# M8300B.net
KiCad netlist of a schematic drawn in EAGLE
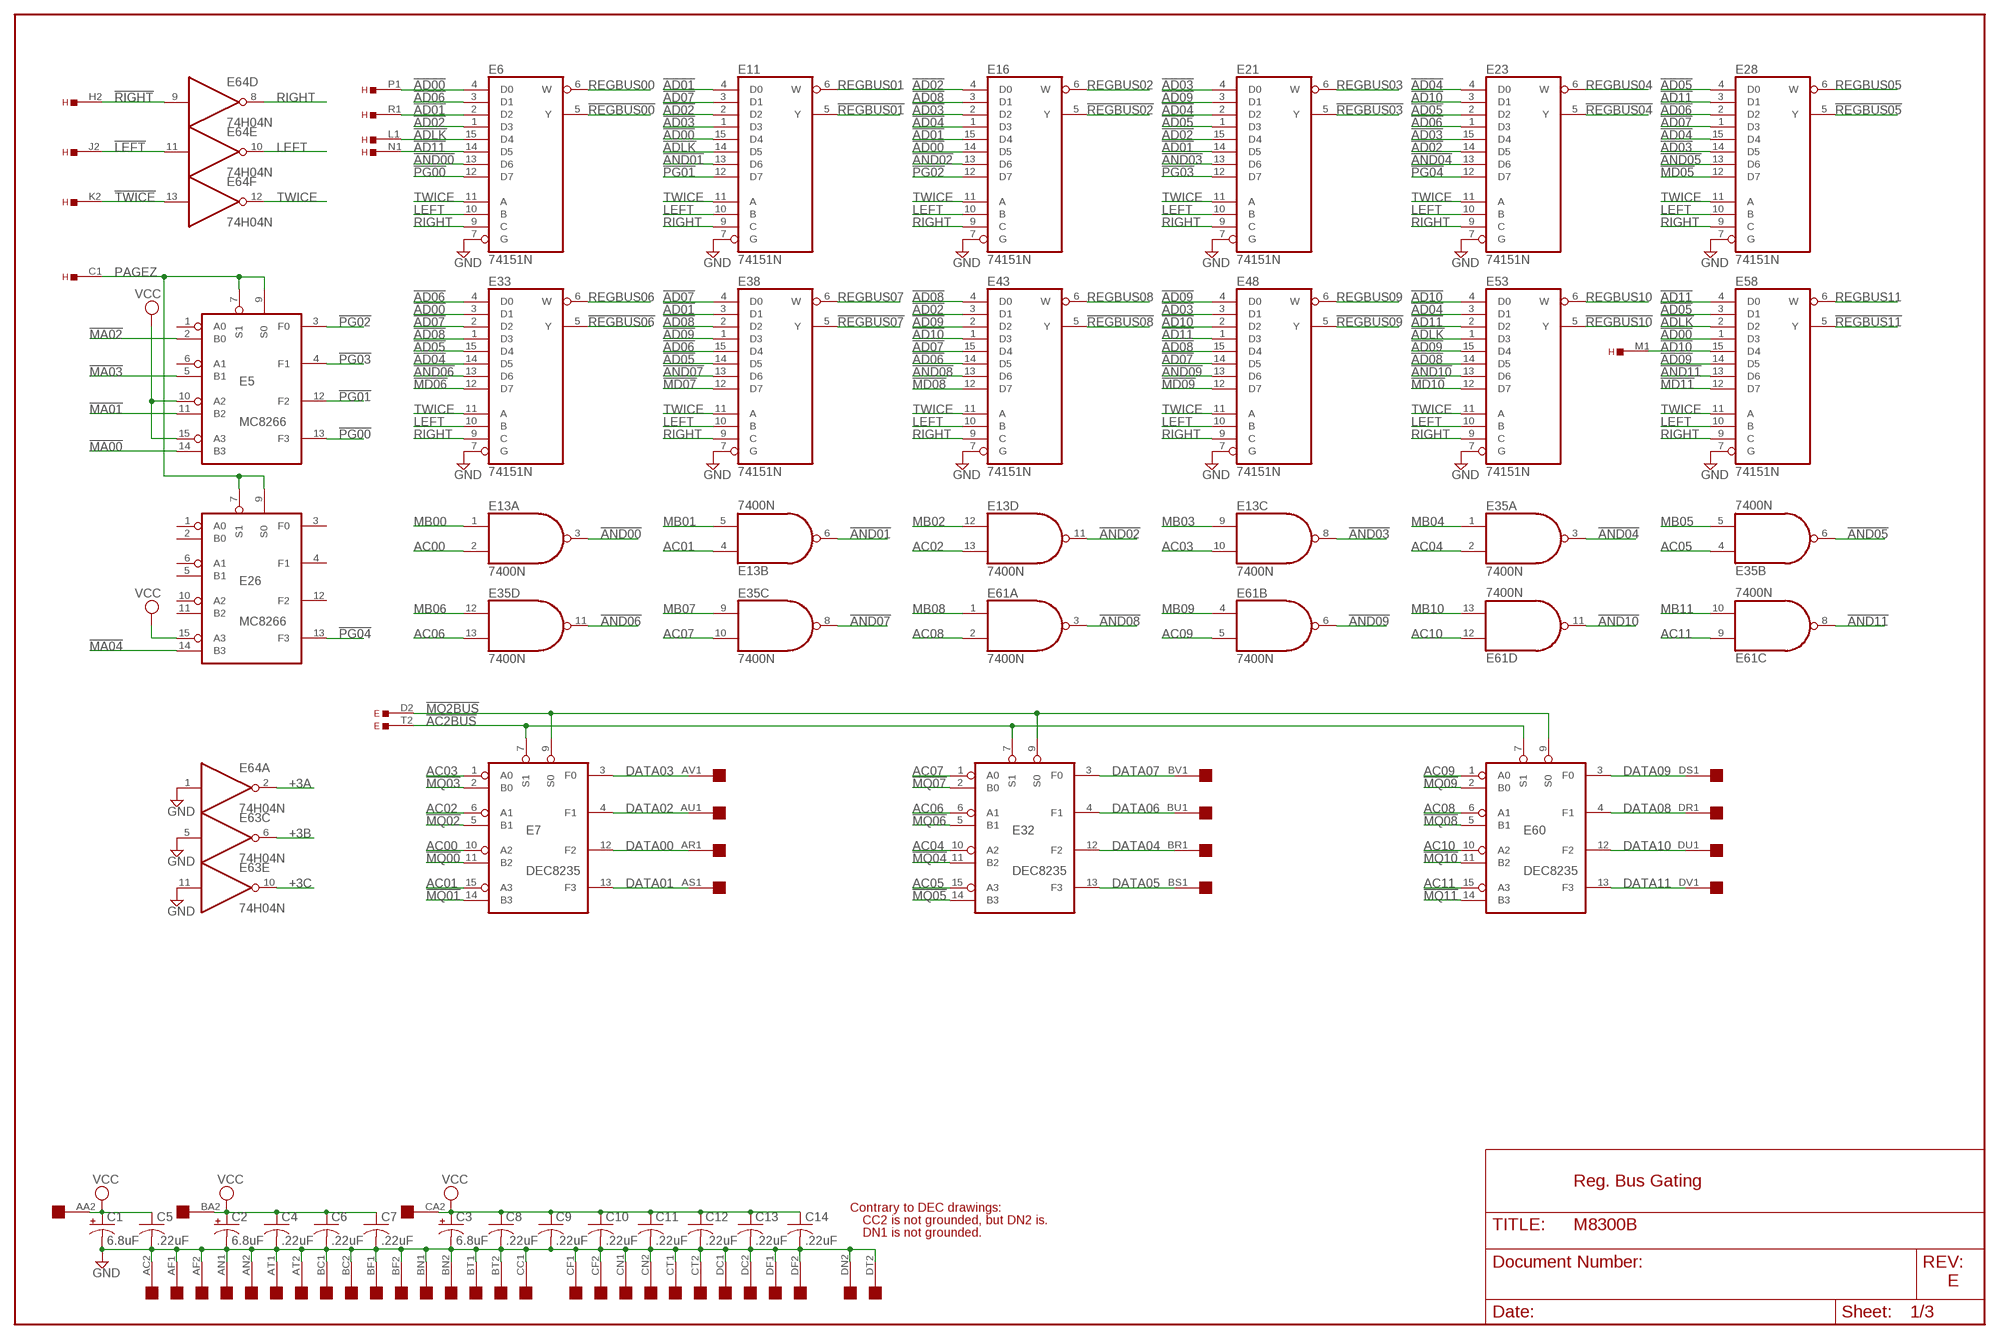
[diagram p0: schematic, sheet 1]
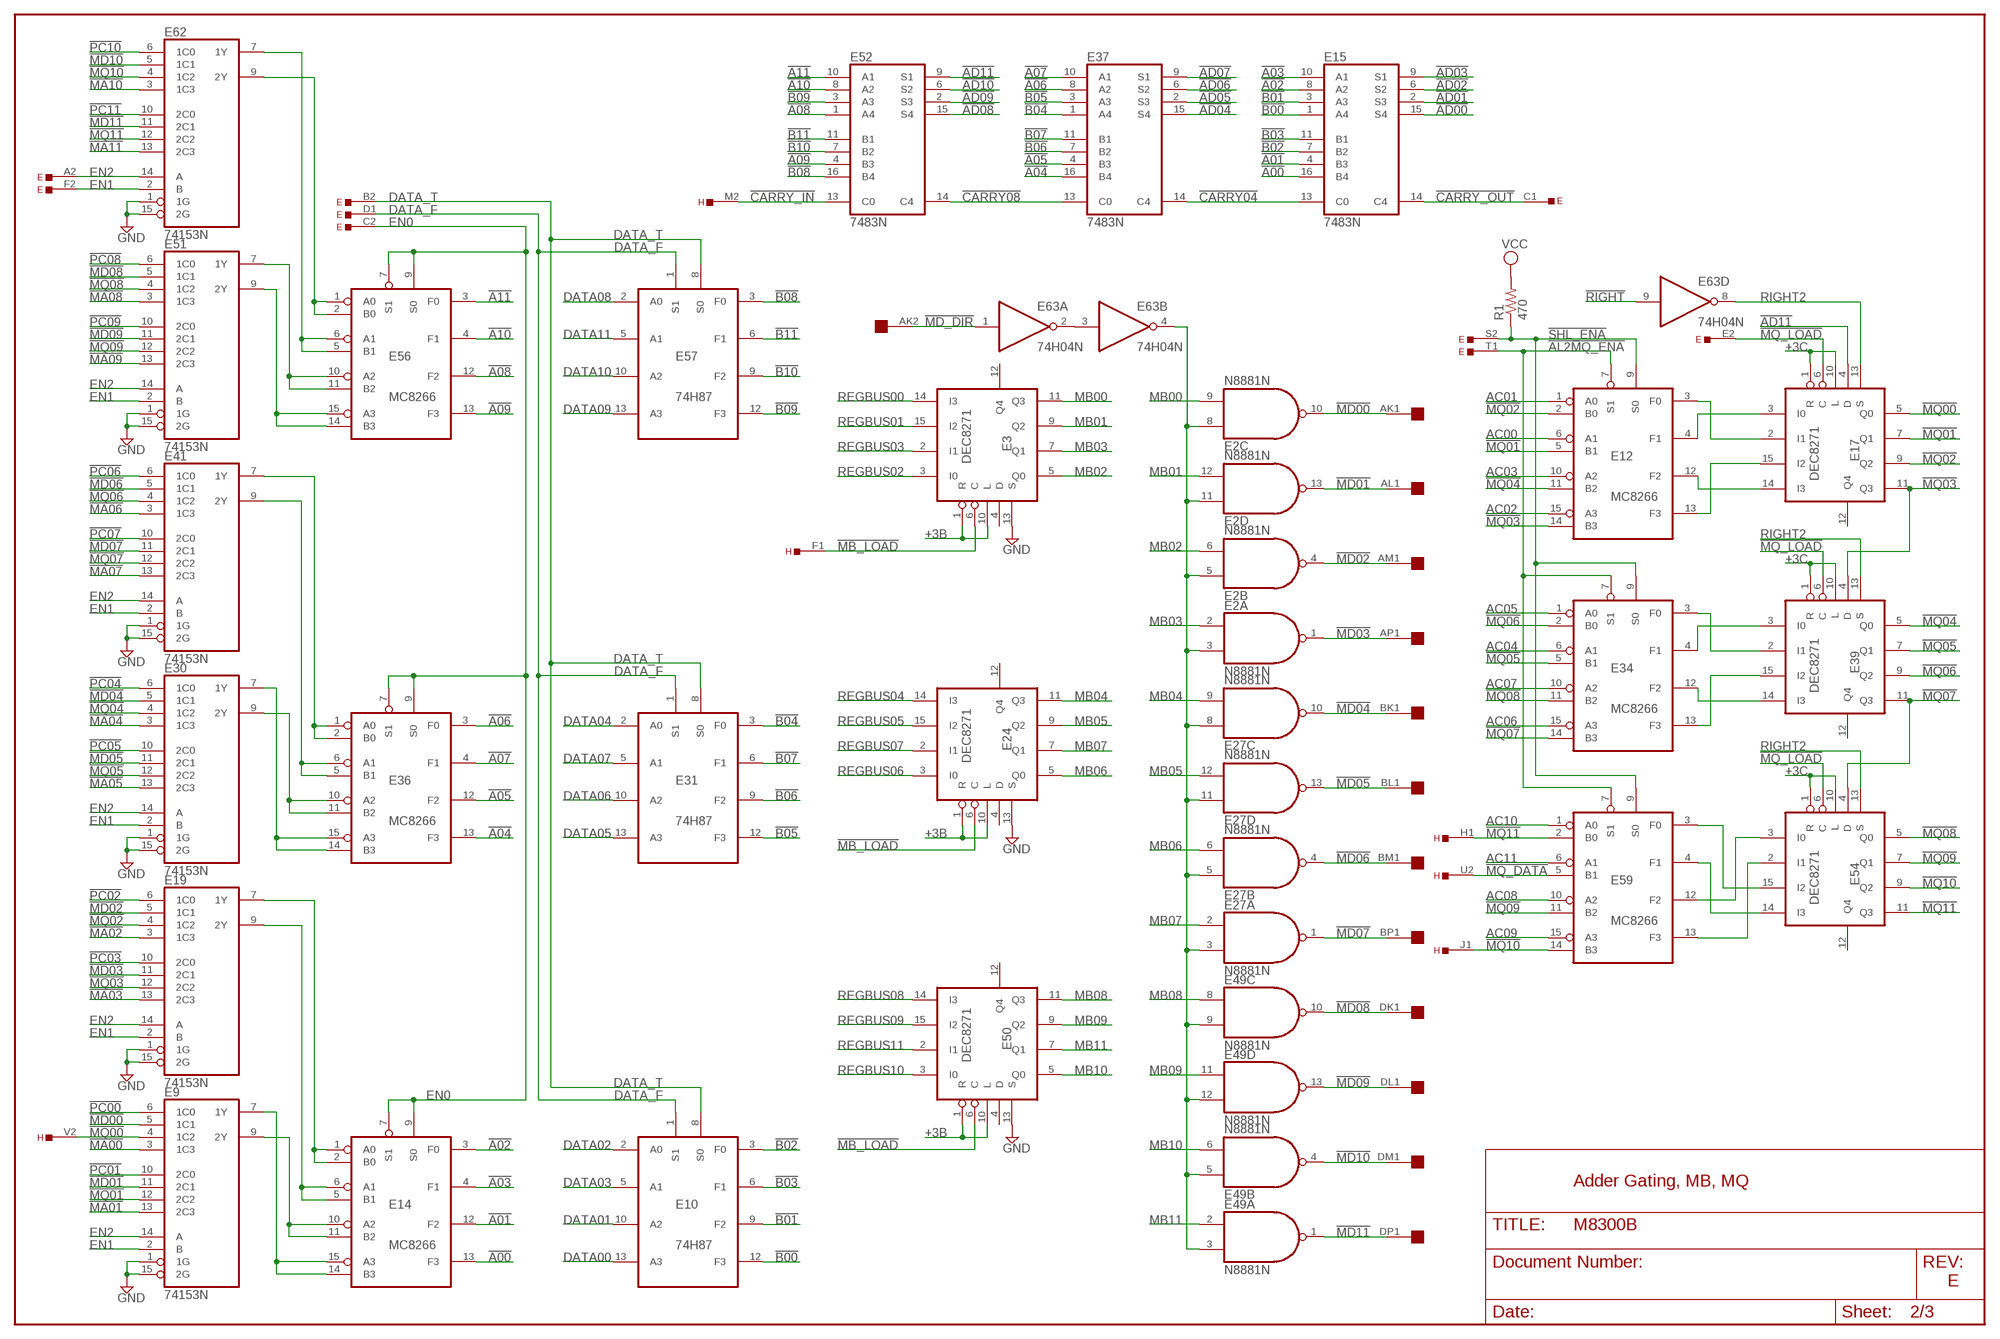
[diagram p1: schematic, sheet 2]
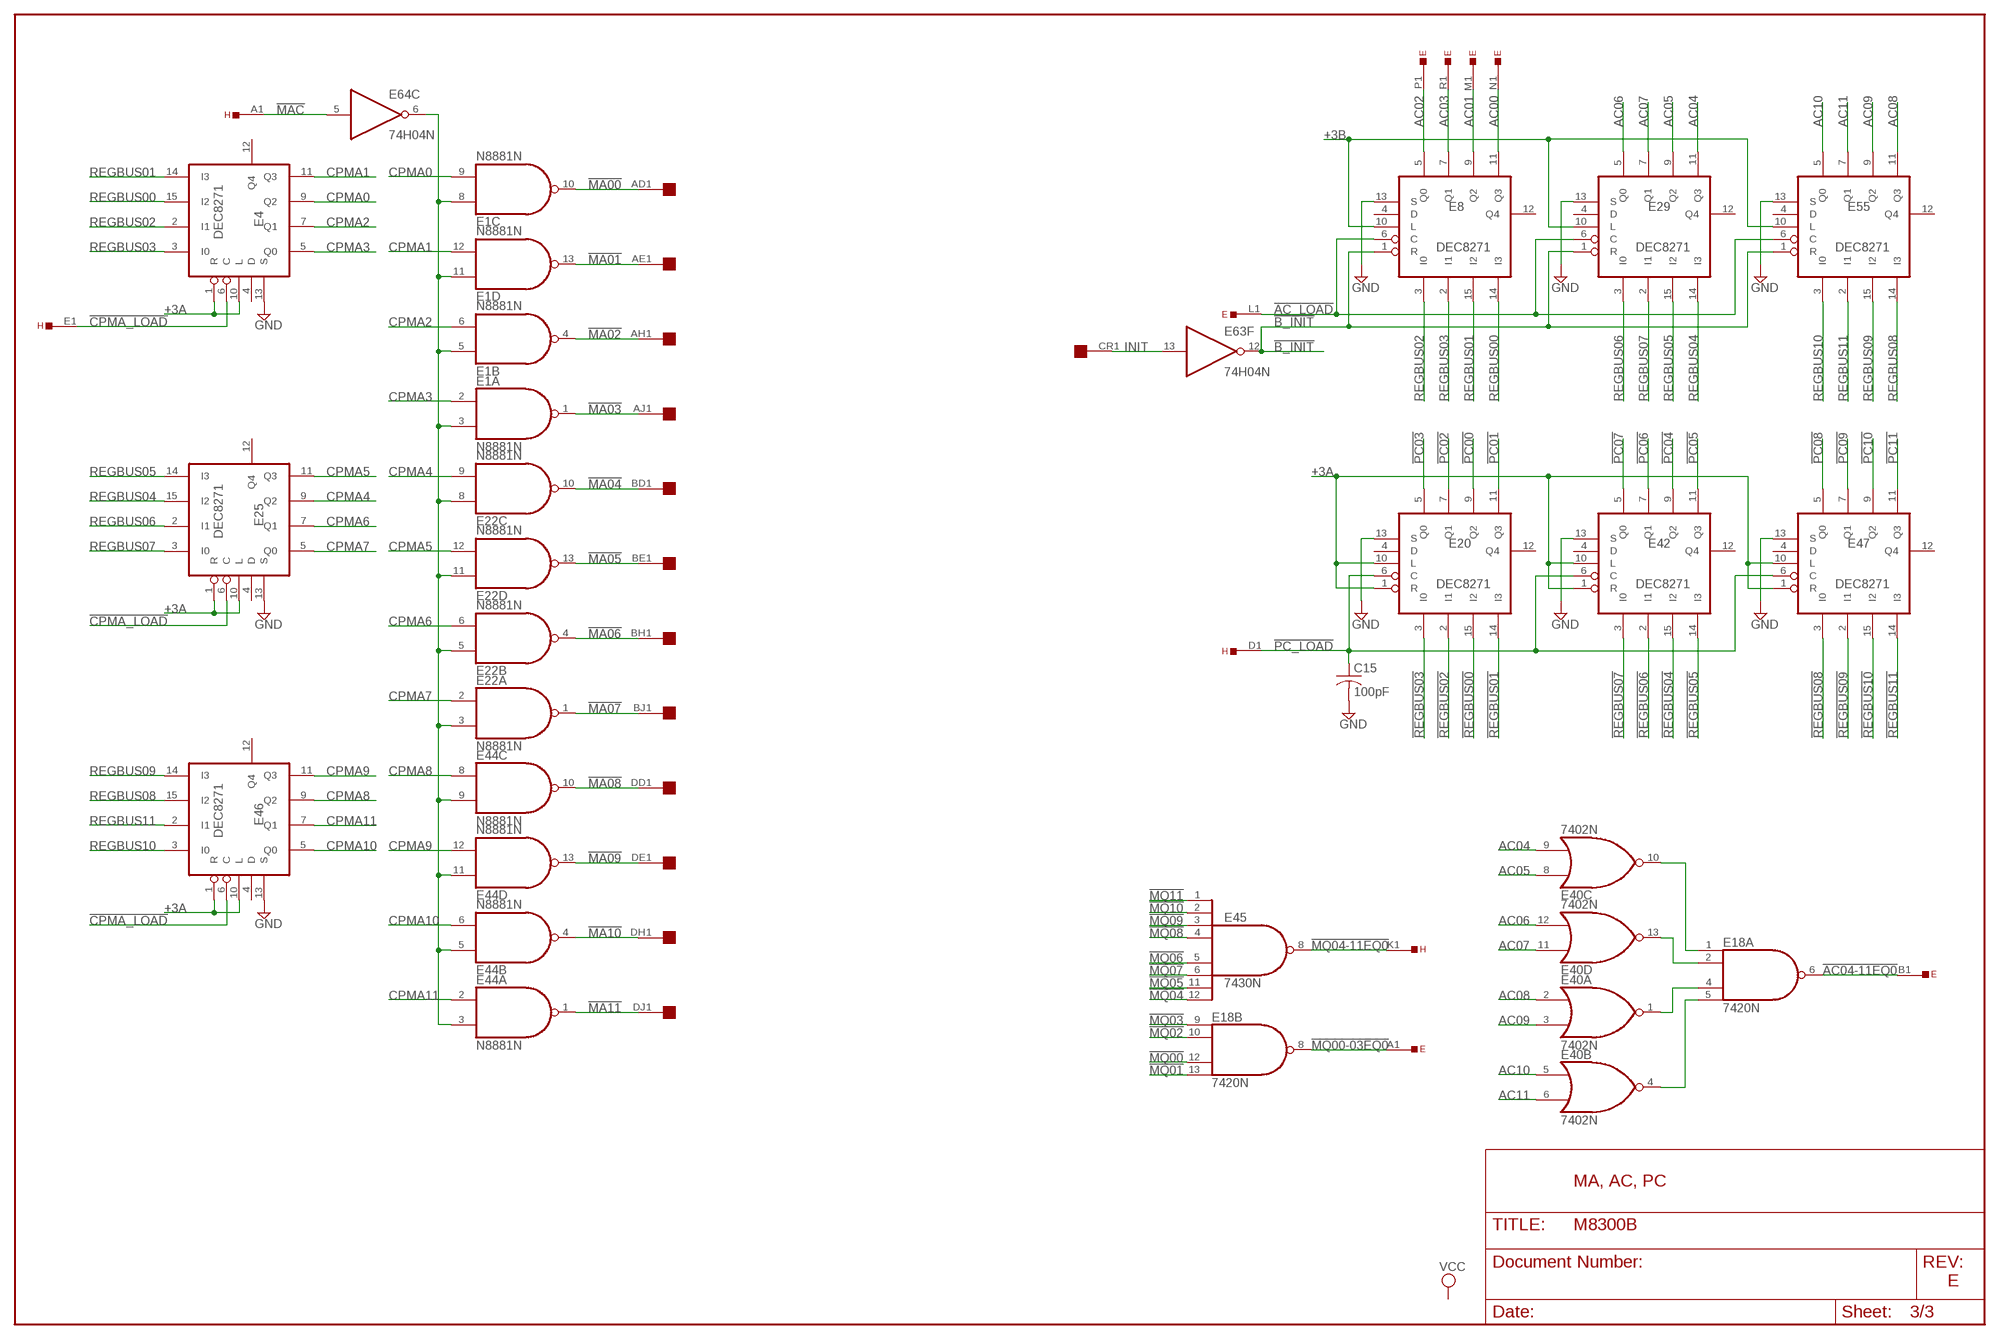
[diagram p2: schematic, sheet 3]

(export (version "E")
  (design (tool "Eeschema 10.0.6"))
  (components
    (comp (ref "E")
      (value "EDGE-TOP")
      (footprint "eagle-import:EDGE-CON2")
      (libsource (lib "eagle-import") (part "EDGE-TOP"))
    )
    (comp (ref "E2")
      (value "N8881N")
      (footprint "eagle-import:DIL14")
      (libsource (lib "eagle-import") (part "N8881N"))
    )
    (comp (ref "E3")
      (value "DEC8271")
      (footprint "eagle-import:DIL16")
      (libsource (lib "eagle-import") (part "DEC8271"))
    )
    (comp (ref "E9")
      (value "74153N")
      (footprint "eagle-import:DIL16")
      (libsource (lib "eagle-import") (part "74153NS"))
    )
    (comp (ref "E10")
      (value "74H87")
      (footprint "eagle-import:DIL14")
      (libsource (lib "eagle-import") (part "7487H"))
    )
    (comp (ref "E12")
      (value "MC8266")
      (footprint "eagle-import:DIL16")
      (libsource (lib "eagle-import") (part "MC8266"))
    )
    (comp (ref "E14")
      (value "MC8266")
      (footprint "eagle-import:DIL16")
      (libsource (lib "eagle-import") (part "MC8266"))
    )
    (comp (ref "E15")
      (value "7483N")
      (footprint "eagle-import:DIL16")
      (libsource (lib "eagle-import") (part "7483N"))
    )
    (comp (ref "E17")
      (value "DEC8271")
      (footprint "eagle-import:DIL16")
      (libsource (lib "eagle-import") (part "DEC8271"))
    )
    (comp (ref "E19")
      (value "74153N")
      (footprint "eagle-import:DIL16")
      (libsource (lib "eagle-import") (part "74153NS"))
    )
    (comp (ref "E24")
      (value "DEC8271")
      (footprint "eagle-import:DIL16")
      (libsource (lib "eagle-import") (part "DEC8271"))
    )
    (comp (ref "E27")
      (value "N8881N")
      (footprint "eagle-import:DIL14")
      (libsource (lib "eagle-import") (part "N8881N"))
    )
    (comp (ref "E30")
      (value "74153N")
      (footprint "eagle-import:DIL16")
      (libsource (lib "eagle-import") (part "74153NS"))
    )
    (comp (ref "E31")
      (value "74H87")
      (footprint "eagle-import:DIL14")
      (libsource (lib "eagle-import") (part "7487H"))
    )
    (comp (ref "E34")
      (value "MC8266")
      (footprint "eagle-import:DIL16")
      (libsource (lib "eagle-import") (part "MC8266"))
    )
    (comp (ref "E36")
      (value "MC8266")
      (footprint "eagle-import:DIL16")
      (libsource (lib "eagle-import") (part "MC8266"))
    )
    (comp (ref "E37")
      (value "7483N")
      (footprint "eagle-import:DIL16")
      (libsource (lib "eagle-import") (part "7483N"))
    )
    (comp (ref "E39")
      (value "DEC8271")
      (footprint "eagle-import:DIL16")
      (libsource (lib "eagle-import") (part "DEC8271"))
    )
    (comp (ref "E41")
      (value "74153N")
      (footprint "eagle-import:DIL16")
      (libsource (lib "eagle-import") (part "74153NS"))
    )
    (comp (ref "E49")
      (value "N8881N")
      (footprint "eagle-import:DIL14")
      (libsource (lib "eagle-import") (part "N8881N"))
    )
    (comp (ref "E50")
      (value "DEC8271")
      (footprint "eagle-import:DIL16")
      (libsource (lib "eagle-import") (part "DEC8271"))
    )
    (comp (ref "E51")
      (value "74153N")
      (footprint "eagle-import:DIL16")
      (libsource (lib "eagle-import") (part "74153NS"))
    )
    (comp (ref "E52")
      (value "7483N")
      (footprint "eagle-import:DIL16")
      (libsource (lib "eagle-import") (part "7483N"))
    )
    (comp (ref "E54")
      (value "DEC8271")
      (footprint "eagle-import:DIL16")
      (libsource (lib "eagle-import") (part "DEC8271"))
    )
    (comp (ref "E56")
      (value "MC8266")
      (footprint "eagle-import:DIL16")
      (libsource (lib "eagle-import") (part "MC8266"))
    )
    (comp (ref "E57")
      (value "74H87")
      (footprint "eagle-import:DIL14")
      (libsource (lib "eagle-import") (part "7487H"))
    )
    (comp (ref "E59")
      (value "MC8266")
      (footprint "eagle-import:DIL16")
      (libsource (lib "eagle-import") (part "MC8266"))
    )
    (comp (ref "E62")
      (value "74153N")
      (footprint "eagle-import:DIL16")
      (libsource (lib "eagle-import") (part "74153NS"))
    )
    (comp (ref "E63")
      (value "74H04N")
      (footprint "eagle-import:DIL14")
      (libsource (lib "eagle-import") (part "7404NS"))
    )
    (comp (ref "H")
      (value "EDGE-TOP")
      (footprint "eagle-import:EDGE-CON2")
      (libsource (lib "eagle-import") (part "EDGE-TOP"))
    )
    (comp (ref "R1")
      (value "470")
      (footprint "eagle-import:0207_10")
      (libsource (lib "eagle-import") (part "R-US_0207/10"))
    )
    (comp (ref "U$2")
      (value "QUAD")
      (footprint "eagle-import:EDGE-CON8")
      (libsource (lib "eagle-import") (part "QUAD"))
    )
    (comp (ref "C15")
      (value "100pF")
      (footprint "eagle-import:C063-025X075")
      (libsource (lib "eagle-import") (part "C-US"))
    )
    (comp (ref "E1")
      (value "N8881N")
      (footprint "eagle-import:DIL14")
      (libsource (lib "eagle-import") (part "N8881N"))
    )
    (comp (ref "E4")
      (value "DEC8271")
      (footprint "eagle-import:DIL16")
      (libsource (lib "eagle-import") (part "DEC8271"))
    )
    (comp (ref "E8")
      (value "DEC8271")
      (footprint "eagle-import:DIL16")
      (libsource (lib "eagle-import") (part "DEC8271"))
    )
    (comp (ref "E18")
      (value "7420N")
      (footprint "eagle-import:DIL14")
      (libsource (lib "eagle-import") (part "7420NS"))
    )
    (comp (ref "E20")
      (value "DEC8271")
      (footprint "eagle-import:DIL16")
      (libsource (lib "eagle-import") (part "DEC8271"))
    )
    (comp (ref "E22")
      (value "N8881N")
      (footprint "eagle-import:DIL14")
      (libsource (lib "eagle-import") (part "N8881N"))
    )
    (comp (ref "E25")
      (value "DEC8271")
      (footprint "eagle-import:DIL16")
      (libsource (lib "eagle-import") (part "DEC8271"))
    )
    (comp (ref "E29")
      (value "DEC8271")
      (footprint "eagle-import:DIL16")
      (libsource (lib "eagle-import") (part "DEC8271"))
    )
    (comp (ref "E40")
      (value "7402N")
      (footprint "eagle-import:DIL14")
      (libsource (lib "eagle-import") (part "7402N"))
    )
    (comp (ref "E42")
      (value "DEC8271")
      (footprint "eagle-import:DIL16")
      (libsource (lib "eagle-import") (part "DEC8271"))
    )
    (comp (ref "E44")
      (value "N8881N")
      (footprint "eagle-import:DIL14")
      (libsource (lib "eagle-import") (part "N8881N"))
    )
    (comp (ref "E45")
      (value "7430N")
      (footprint "eagle-import:DIL14")
      (libsource (lib "eagle-import") (part "7430N"))
    )
    (comp (ref "E46")
      (value "DEC8271")
      (footprint "eagle-import:DIL16")
      (libsource (lib "eagle-import") (part "DEC8271"))
    )
    (comp (ref "E47")
      (value "DEC8271")
      (footprint "eagle-import:DIL16")
      (libsource (lib "eagle-import") (part "DEC8271"))
    )
    (comp (ref "E55")
      (value "DEC8271")
      (footprint "eagle-import:DIL16")
      (libsource (lib "eagle-import") (part "DEC8271"))
    )
    (comp (ref "E64")
      (value "74H04N")
      (footprint "eagle-import:DIL14")
      (libsource (lib "eagle-import") (part "7404NS"))
    )
    (comp (ref "C1")
      (value "6.8uF")
      (footprint "eagle-import:E12-8")
      (libsource (lib "eagle-import") (part "CPOL-USE20-8AXIAL"))
    )
    (comp (ref "C2")
      (value "6.8uF")
      (footprint "eagle-import:E12-8")
      (libsource (lib "eagle-import") (part "CPOL-USE20-8AXIAL"))
    )
    (comp (ref "C3")
      (value "6.8uF")
      (footprint "eagle-import:E12-8")
      (libsource (lib "eagle-import") (part "CPOL-USE20-8AXIAL"))
    )
    (comp (ref "C4")
      (value ".22uF")
      (footprint "eagle-import:C063-025X075")
      (libsource (lib "eagle-import") (part "C-US"))
    )
    (comp (ref "C5")
      (value ".22uF")
      (footprint "eagle-import:C063-025X075")
      (libsource (lib "eagle-import") (part "C-US"))
    )
    (comp (ref "C6")
      (value ".22uF")
      (footprint "eagle-import:C063-025X075")
      (libsource (lib "eagle-import") (part "C-US"))
    )
    (comp (ref "C7")
      (value ".22uF")
      (footprint "eagle-import:C063-025X075")
      (libsource (lib "eagle-import") (part "C-US"))
    )
    (comp (ref "C8")
      (value ".22uF")
      (footprint "eagle-import:C063-025X075")
      (libsource (lib "eagle-import") (part "C-US"))
    )
    (comp (ref "C9")
      (value ".22uF")
      (footprint "eagle-import:C063-025X075")
      (libsource (lib "eagle-import") (part "C-US"))
    )
    (comp (ref "C10")
      (value ".22uF")
      (footprint "eagle-import:C063-025X075")
      (libsource (lib "eagle-import") (part "C-US"))
    )
    (comp (ref "C11")
      (value ".22uF")
      (footprint "eagle-import:C063-025X075")
      (libsource (lib "eagle-import") (part "C-US"))
    )
    (comp (ref "C12")
      (value ".22uF")
      (footprint "eagle-import:C063-025X075")
      (libsource (lib "eagle-import") (part "C-US"))
    )
    (comp (ref "C13")
      (value ".22uF")
      (footprint "eagle-import:C063-025X075")
      (libsource (lib "eagle-import") (part "C-US"))
    )
    (comp (ref "C14")
      (value ".22uF")
      (footprint "eagle-import:C063-025X075")
      (libsource (lib "eagle-import") (part "C-US"))
    )
    (comp (ref "E5")
      (value "MC8266")
      (footprint "eagle-import:DIL16")
      (libsource (lib "eagle-import") (part "MC8266"))
    )
    (comp (ref "E6")
      (value "74151N")
      (footprint "eagle-import:DIL16")
      (libsource (lib "eagle-import") (part "74151N"))
    )
    (comp (ref "E7")
      (value "DEC8235")
      (footprint "eagle-import:DIL16")
      (libsource (lib "eagle-import") (part "DEC8235"))
    )
    (comp (ref "E11")
      (value "74151N")
      (footprint "eagle-import:DIL16")
      (libsource (lib "eagle-import") (part "74151N"))
    )
    (comp (ref "E13")
      (value "7400N")
      (footprint "eagle-import:DIL14")
      (libsource (lib "eagle-import") (part "7400N"))
    )
    (comp (ref "E16")
      (value "74151N")
      (footprint "eagle-import:DIL16")
      (libsource (lib "eagle-import") (part "74151N"))
    )
    (comp (ref "E21")
      (value "74151N")
      (footprint "eagle-import:DIL16")
      (libsource (lib "eagle-import") (part "74151N"))
    )
    (comp (ref "E23")
      (value "74151N")
      (footprint "eagle-import:DIL16")
      (libsource (lib "eagle-import") (part "74151N"))
    )
    (comp (ref "E26")
      (value "MC8266")
      (footprint "eagle-import:DIL16")
      (libsource (lib "eagle-import") (part "MC8266"))
    )
    (comp (ref "E28")
      (value "74151N")
      (footprint "eagle-import:DIL16")
      (libsource (lib "eagle-import") (part "74151N"))
    )
    (comp (ref "E32")
      (value "DEC8235")
      (footprint "eagle-import:DIL16")
      (libsource (lib "eagle-import") (part "DEC8235"))
    )
    (comp (ref "E33")
      (value "74151N")
      (footprint "eagle-import:DIL16")
      (libsource (lib "eagle-import") (part "74151N"))
    )
    (comp (ref "E35")
      (value "7400N")
      (footprint "eagle-import:DIL14")
      (libsource (lib "eagle-import") (part "7400N"))
    )
    (comp (ref "E38")
      (value "74151N")
      (footprint "eagle-import:DIL16")
      (libsource (lib "eagle-import") (part "74151N"))
    )
    (comp (ref "E43")
      (value "74151N")
      (footprint "eagle-import:DIL16")
      (libsource (lib "eagle-import") (part "74151N"))
    )
    (comp (ref "E48")
      (value "74151N")
      (footprint "eagle-import:DIL16")
      (libsource (lib "eagle-import") (part "74151N"))
    )
    (comp (ref "E53")
      (value "74151N")
      (footprint "eagle-import:DIL16")
      (libsource (lib "eagle-import") (part "74151N"))
    )
    (comp (ref "E58")
      (value "74151N")
      (footprint "eagle-import:DIL16")
      (libsource (lib "eagle-import") (part "74151N"))
    )
    (comp (ref "E60")
      (value "DEC8235")
      (footprint "eagle-import:DIL16")
      (libsource (lib "eagle-import") (part "DEC8235"))
    )
    (comp (ref "E61")
      (value "7400N")
      (footprint "eagle-import:DIL14")
      (libsource (lib "eagle-import") (part "7400N"))
    )
  )
  (nets
    (net (code "1") (name "+3A") (class "Default")
      (node (ref "E20") (pin "1") (pinfunction "R_1") (pintype "input"))
      (node (ref "E20") (pin "10") (pinfunction "L_10") (pintype "input"))
      (node (ref "E25") (pin "1") (pinfunction "R_1") (pintype "input"))
      (node (ref "E25") (pin "10") (pinfunction "L_10") (pintype "input"))
      (node (ref "E4") (pin "1") (pinfunction "R_1") (pintype "input"))
      (node (ref "E4") (pin "10") (pinfunction "L_10") (pintype "input"))
      (node (ref "E42") (pin "1") (pinfunction "R_1") (pintype "input"))
      (node (ref "E42") (pin "10") (pinfunction "L_10") (pintype "input"))
      (node (ref "E46") (pin "1") (pinfunction "R_1") (pintype "input"))
      (node (ref "E46") (pin "10") (pinfunction "L_10") (pintype "input"))
      (node (ref "E47") (pin "1") (pinfunction "R_1") (pintype "input"))
      (node (ref "E47") (pin "10") (pinfunction "L_10") (pintype "input"))
      (node (ref "E64") (pin "2") (pinfunction "O_2") (pintype "output"))
    )
    (net (code "2") (name "+3B") (class "Default")
      (node (ref "E24") (pin "1") (pinfunction "R_1") (pintype "input"))
      (node (ref "E24") (pin "10") (pinfunction "L_10") (pintype "input"))
      (node (ref "E29") (pin "10") (pinfunction "L_10") (pintype "input"))
      (node (ref "E3") (pin "1") (pinfunction "R_1") (pintype "input"))
      (node (ref "E3") (pin "10") (pinfunction "L_10") (pintype "input"))
      (node (ref "E50") (pin "1") (pinfunction "R_1") (pintype "input"))
      (node (ref "E50") (pin "10") (pinfunction "L_10") (pintype "input"))
      (node (ref "E55") (pin "10") (pinfunction "L_10") (pintype "input"))
      (node (ref "E63") (pin "6") (pinfunction "O_6") (pintype "output"))
      (node (ref "E8") (pin "10") (pinfunction "L_10") (pintype "input"))
    )
    (net (code "3") (name "+3C") (class "Default")
      (node (ref "E17") (pin "1") (pinfunction "R_1") (pintype "input"))
      (node (ref "E17") (pin "10") (pinfunction "L_10") (pintype "input"))
      (node (ref "E39") (pin "1") (pinfunction "R_1") (pintype "input"))
      (node (ref "E39") (pin "10") (pinfunction "L_10") (pintype "input"))
      (node (ref "E54") (pin "1") (pinfunction "R_1") (pintype "input"))
      (node (ref "E54") (pin "10") (pinfunction "L_10") (pintype "input"))
      (node (ref "E63") (pin "10") (pinfunction "O_10") (pintype "output"))
    )
    (net (code "4") (name "AC00") (class "Default")
      (node (ref "E") (pin "N1") (pinfunction "P_N1") (pintype "passive"))
      (node (ref "E12") (pin "6") (pinfunction "A1_6") (pintype "input"))
      (node (ref "E13") (pin "2") (pinfunction "I1_2") (pintype "input"))
      (node (ref "E7") (pin "10") (pinfunction "A2_10") (pintype "input"))
      (node (ref "E8") (pin "11") (pinfunction "Q3_11") (pintype "output"))
    )
    (net (code "5") (name "AC01") (class "Default")
      (node (ref "E") (pin "M1") (pinfunction "P_M1") (pintype "passive"))
      (node (ref "E12") (pin "1") (pinfunction "A0_1") (pintype "input"))
      (node (ref "E13") (pin "4") (pinfunction "I0_4") (pintype "input"))
      (node (ref "E7") (pin "15") (pinfunction "A3_15") (pintype "input"))
      (node (ref "E8") (pin "9") (pinfunction "Q2_9") (pintype "output"))
    )
    (net (code "6") (name "AC02") (class "Default")
      (node (ref "E") (pin "P1") (pinfunction "P_P1") (pintype "passive"))
      (node (ref "E12") (pin "15") (pinfunction "A3_15") (pintype "input"))
      (node (ref "E13") (pin "13") (pinfunction "I1_13") (pintype "input"))
      (node (ref "E7") (pin "6") (pinfunction "A1_6") (pintype "input"))
      (node (ref "E8") (pin "5") (pinfunction "Q0_5") (pintype "output"))
    )
    (net (code "7") (name "AC03") (class "Default")
      (node (ref "E") (pin "R1") (pinfunction "P_R1") (pintype "passive"))
      (node (ref "E12") (pin "10") (pinfunction "A2_10") (pintype "input"))
      (node (ref "E13") (pin "10") (pinfunction "I1_10") (pintype "input"))
      (node (ref "E7") (pin "1") (pinfunction "A0_1") (pintype "input"))
      (node (ref "E8") (pin "7") (pinfunction "Q1_7") (pintype "output"))
    )
    (net (code "8") (name "AC04") (class "Default")
      (node (ref "E29") (pin "11") (pinfunction "Q3_11") (pintype "output"))
      (node (ref "E32") (pin "10") (pinfunction "A2_10") (pintype "input"))
      (node (ref "E34") (pin "6") (pinfunction "A1_6") (pintype "input"))
      (node (ref "E35") (pin "2") (pinfunction "I1_2") (pintype "input"))
      (node (ref "E40") (pin "9") (pinfunction "I1_9") (pintype "input"))
    )
    (net (code "9") (name "AC05") (class "Default")
      (node (ref "E29") (pin "9") (pinfunction "Q2_9") (pintype "output"))
      (node (ref "E32") (pin "15") (pinfunction "A3_15") (pintype "input"))
      (node (ref "E34") (pin "1") (pinfunction "A0_1") (pintype "input"))
      (node (ref "E35") (pin "4") (pinfunction "I0_4") (pintype "input"))
      (node (ref "E40") (pin "8") (pinfunction "I0_8") (pintype "input"))
    )
    (net (code "10") (name "AC06") (class "Default")
      (node (ref "E29") (pin "5") (pinfunction "Q0_5") (pintype "output"))
      (node (ref "E32") (pin "6") (pinfunction "A1_6") (pintype "input"))
      (node (ref "E34") (pin "15") (pinfunction "A3_15") (pintype "input"))
      (node (ref "E35") (pin "13") (pinfunction "I1_13") (pintype "input"))
      (node (ref "E40") (pin "12") (pinfunction "I1_12") (pintype "input"))
    )
    (net (code "11") (name "AC07") (class "Default")
      (node (ref "E29") (pin "7") (pinfunction "Q1_7") (pintype "output"))
      (node (ref "E32") (pin "1") (pinfunction "A0_1") (pintype "input"))
      (node (ref "E34") (pin "10") (pinfunction "A2_10") (pintype "input"))
      (node (ref "E35") (pin "10") (pinfunction "I1_10") (pintype "input"))
      (node (ref "E40") (pin "11") (pinfunction "I0_11") (pintype "input"))
    )
    (net (code "12") (name "AC08") (class "Default")
      (node (ref "E40") (pin "2") (pinfunction "I0_2") (pintype "input"))
      (node (ref "E55") (pin "11") (pinfunction "Q3_11") (pintype "output"))
      (node (ref "E59") (pin "10") (pinfunction "A2_10") (pintype "input"))
      (node (ref "E60") (pin "6") (pinfunction "A1_6") (pintype "input"))
      (node (ref "E61") (pin "2") (pinfunction "I1_2") (pintype "input"))
    )
    (net (code "13") (name "AC09") (class "Default")
      (node (ref "E40") (pin "3") (pinfunction "I1_3") (pintype "input"))
      (node (ref "E55") (pin "9") (pinfunction "Q2_9") (pintype "output"))
      (node (ref "E59") (pin "15") (pinfunction "A3_15") (pintype "input"))
      (node (ref "E60") (pin "1") (pinfunction "A0_1") (pintype "input"))
      (node (ref "E61") (pin "5") (pinfunction "I1_5") (pintype "input"))
    )
    (net (code "14") (name "AC10") (class "Default")
      (node (ref "E40") (pin "5") (pinfunction "I0_5") (pintype "input"))
      (node (ref "E55") (pin "5") (pinfunction "Q0_5") (pintype "output"))
      (node (ref "E59") (pin "1") (pinfunction "A0_1") (pintype "input"))
      (node (ref "E60") (pin "10") (pinfunction "A2_10") (pintype "input"))
      (node (ref "E61") (pin "12") (pinfunction "I0_12") (pintype "input"))
    )
    (net (code "15") (name "AC11") (class "Default")
      (node (ref "E40") (pin "6") (pinfunction "I1_6") (pintype "input"))
      (node (ref "E55") (pin "7") (pinfunction "Q1_7") (pintype "output"))
      (node (ref "E59") (pin "6") (pinfunction "A1_6") (pintype "input"))
      (node (ref "E60") (pin "15") (pinfunction "A3_15") (pintype "input"))
      (node (ref "E61") (pin "9") (pinfunction "I0_9") (pintype "input"))
    )
    (net (code "16") (name "CPMA0") (class "Default")
      (node (ref "E1") (pin "9") (pinfunction "I1_9") (pintype "input"))
      (node (ref "E4") (pin "9") (pinfunction "Q2_9") (pintype "output"))
    )
    (net (code "17") (name "CPMA1") (class "Default")
      (node (ref "E1") (pin "12") (pinfunction "I1_12") (pintype "input"))
      (node (ref "E4") (pin "11") (pinfunction "Q3_11") (pintype "output"))
    )
    (net (code "18") (name "CPMA2") (class "Default")
      (node (ref "E1") (pin "6") (pinfunction "I1_6") (pintype "input"))
      (node (ref "E4") (pin "7") (pinfunction "Q1_7") (pintype "output"))
    )
    (net (code "19") (name "CPMA3") (class "Default")
      (node (ref "E1") (pin "2") (pinfunction "I0_2") (pintype "input"))
      (node (ref "E4") (pin "5") (pinfunction "Q0_5") (pintype "output"))
    )
    (net (code "20") (name "CPMA4") (class "Default")
      (node (ref "E22") (pin "9") (pinfunction "I1_9") (pintype "input"))
      (node (ref "E25") (pin "9") (pinfunction "Q2_9") (pintype "output"))
    )
    (net (code "21") (name "CPMA5") (class "Default")
      (node (ref "E22") (pin "12") (pinfunction "I1_12") (pintype "input"))
      (node (ref "E25") (pin "11") (pinfunction "Q3_11") (pintype "output"))
    )
    (net (code "22") (name "CPMA6") (class "Default")
      (node (ref "E22") (pin "6") (pinfunction "I1_6") (pintype "input"))
      (node (ref "E25") (pin "7") (pinfunction "Q1_7") (pintype "output"))
    )
    (net (code "23") (name "CPMA7") (class "Default")
      (node (ref "E22") (pin "2") (pinfunction "I0_2") (pintype "input"))
      (node (ref "E25") (pin "5") (pinfunction "Q0_5") (pintype "output"))
    )
    (net (code "24") (name "CPMA8") (class "Default")
      (node (ref "E44") (pin "8") (pinfunction "I0_8") (pintype "input"))
      (node (ref "E46") (pin "9") (pinfunction "Q2_9") (pintype "output"))
    )
    (net (code "25") (name "CPMA9") (class "Default")
      (node (ref "E44") (pin "12") (pinfunction "I1_12") (pintype "input"))
      (node (ref "E46") (pin "11") (pinfunction "Q3_11") (pintype "output"))
    )
    (net (code "26") (name "CPMA10") (class "Default")
      (node (ref "E44") (pin "6") (pinfunction "I1_6") (pintype "input"))
      (node (ref "E46") (pin "5") (pinfunction "Q0_5") (pintype "output"))
    )
    (net (code "27") (name "CPMA11") (class "Default")
      (node (ref "E44") (pin "2") (pinfunction "I0_2") (pintype "input"))
      (node (ref "E46") (pin "7") (pinfunction "Q1_7") (pintype "output"))
    )
    (net (code "28") (name "DATA00") (class "Default")
      (node (ref "E10") (pin "13") (pinfunction "A3_13") (pintype "input"))
      (node (ref "E7") (pin "12") (pinfunction "F2_12") (pintype "open_collector"))
      (node (ref "U$2") (pin "AR1") (pinfunction "1_AR1") (pintype "bidirectional"))
    )
    (net (code "29") (name "DATA01") (class "Default")
      (node (ref "E10") (pin "10") (pinfunction "A2_10") (pintype "input"))
      (node (ref "E7") (pin "13") (pinfunction "F3_13") (pintype "open_collector"))
      (node (ref "U$2") (pin "AS1") (pinfunction "1_AS1") (pintype "bidirectional"))
    )
    (net (code "30") (name "DATA02") (class "Default")
      (node (ref "E10") (pin "2") (pinfunction "A0_2") (pintype "input"))
      (node (ref "E7") (pin "4") (pinfunction "F1_4") (pintype "open_collector"))
      (node (ref "U$2") (pin "AU1") (pinfunction "1_AU1") (pintype "bidirectional"))
    )
    (net (code "31") (name "DATA03") (class "Default")
      (node (ref "E10") (pin "5") (pinfunction "A1_5") (pintype "input"))
      (node (ref "E7") (pin "3") (pinfunction "F0_3") (pintype "open_collector"))
      (node (ref "U$2") (pin "AV1") (pinfunction "1_AV1") (pintype "bidirectional"))
    )
    (net (code "32") (name "DATA04") (class "Default")
      (node (ref "E31") (pin "2") (pinfunction "A0_2") (pintype "input"))
      (node (ref "E32") (pin "12") (pinfunction "F2_12") (pintype "open_collector"))
      (node (ref "U$2") (pin "BR1") (pinfunction "1_BR1") (pintype "bidirectional"))
    )
    (net (code "33") (name "DATA05") (class "Default")
      (node (ref "E31") (pin "13") (pinfunction "A3_13") (pintype "input"))
      (node (ref "E32") (pin "13") (pinfunction "F3_13") (pintype "open_collector"))
      (node (ref "U$2") (pin "BS1") (pinfunction "1_BS1") (pintype "bidirectional"))
    )
    (net (code "34") (name "DATA06") (class "Default")
      (node (ref "E31") (pin "10") (pinfunction "A2_10") (pintype "input"))
      (node (ref "E32") (pin "4") (pinfunction "F1_4") (pintype "open_collector"))
      (node (ref "U$2") (pin "BU1") (pinfunction "1_BU1") (pintype "bidirectional"))
    )
    (net (code "35") (name "DATA07") (class "Default")
      (node (ref "E31") (pin "5") (pinfunction "A1_5") (pintype "input"))
      (node (ref "E32") (pin "3") (pinfunction "F0_3") (pintype "open_collector"))
      (node (ref "U$2") (pin "BV1") (pinfunction "1_BV1") (pintype "bidirectional"))
    )
    (net (code "36") (name "DATA08") (class "Default")
      (node (ref "E57") (pin "2") (pinfunction "A0_2") (pintype "input"))
      (node (ref "E60") (pin "4") (pinfunction "F1_4") (pintype "open_collector"))
      (node (ref "U$2") (pin "DR1") (pinfunction "1_DR1") (pintype "bidirectional"))
    )
    (net (code "37") (name "DATA09") (class "Default")
      (node (ref "E57") (pin "13") (pinfunction "A3_13") (pintype "input"))
      (node (ref "E60") (pin "3") (pinfunction "F0_3") (pintype "open_collector"))
      (node (ref "U$2") (pin "DS1") (pinfunction "1_DS1") (pintype "bidirectional"))
    )
    (net (code "38") (name "DATA10") (class "Default")
      (node (ref "E57") (pin "10") (pinfunction "A2_10") (pintype "input"))
      (node (ref "E60") (pin "12") (pinfunction "F2_12") (pintype "open_collector"))
      (node (ref "U$2") (pin "DU1") (pinfunction "1_DU1") (pintype "bidirectional"))
    )
    (net (code "39") (name "DATA11") (class "Default")
      (node (ref "E57") (pin "5") (pinfunction "A1_5") (pintype "input"))
      (node (ref "E60") (pin "13") (pinfunction "F3_13") (pintype "open_collector"))
      (node (ref "U$2") (pin "DV1") (pinfunction "1_DV1") (pintype "bidirectional"))
    )
    (net (code "40") (name "DATA_F") (class "Default")
      (node (ref "E") (pin "D1") (pinfunction "P_D1") (pintype "passive"))
      (node (ref "E10") (pin "1") (pinfunction "S1_1") (pintype "input"))
      (node (ref "E31") (pin "1") (pinfunction "S1_1") (pintype "input"))
      (node (ref "E57") (pin "1") (pinfunction "S1_1") (pintype "input"))
    )
    (net (code "41") (name "DATA_T") (class "Default")
      (node (ref "E") (pin "B2") (pinfunction "P_B2") (pintype "passive"))
      (node (ref "E10") (pin "8") (pinfunction "S0_8") (pintype "input"))
      (node (ref "E31") (pin "8") (pinfunction "S0_8") (pintype "input"))
      (node (ref "E57") (pin "8") (pinfunction "S0_8") (pintype "input"))
    )
    (net (code "42") (name "EN0") (class "Default")
      (node (ref "E") (pin "C2") (pinfunction "P_C2") (pintype "passive"))
      (node (ref "E14") (pin "7") (pinfunction "S1_7") (pintype "input"))
      (node (ref "E14") (pin "9") (pinfunction "S0_9") (pintype "input"))
      (node (ref "E36") (pin "7") (pinfunction "S1_7") (pintype "input"))
      (node (ref "E36") (pin "9") (pinfunction "S0_9") (pintype "input"))
      (node (ref "E56") (pin "7") (pinfunction "S1_7") (pintype "input"))
      (node (ref "E56") (pin "9") (pinfunction "S0_9") (pintype "input"))
    )
    (net (code "43") (name "EN1") (class "Default")
      (node (ref "E") (pin "F2") (pinfunction "P_F2") (pintype "passive"))
      (node (ref "E19") (pin "2") (pinfunction "B_2") (pintype "input"))
      (node (ref "E30") (pin "2") (pinfunction "B_2") (pintype "input"))
      (node (ref "E41") (pin "2") (pinfunction "B_2") (pintype "input"))
      (node (ref "E51") (pin "2") (pinfunction "B_2") (pintype "input"))
      (node (ref "E62") (pin "2") (pinfunction "B_2") (pintype "input"))
      (node (ref "E9") (pin "2") (pinfunction "B_2") (pintype "input"))
    )
    (net (code "44") (name "EN2") (class "Default")
      (node (ref "E") (pin "A2") (pinfunction "P_A2") (pintype "passive"))
      (node (ref "E19") (pin "14") (pinfunction "A_14") (pintype "input"))
      (node (ref "E30") (pin "14") (pinfunction "A_14") (pintype "input"))
      (node (ref "E41") (pin "14") (pinfunction "A_14") (pintype "input"))
      (node (ref "E51") (pin "14") (pinfunction "A_14") (pintype "input"))
      (node (ref "E62") (pin "14") (pinfunction "A_14") (pintype "input"))
      (node (ref "E9") (pin "14") (pinfunction "A_14") (pintype "input"))
    )
    (net (code "45") (name "GND") (class "Default")
      (node (ref "C1") (pin "-") (pinfunction "-_-") (pintype "passive"))
      (node (ref "C10") (pin "2") (pinfunction "2_2") (pintype "passive"))
      (node (ref "C11") (pin "2") (pinfunction "2_2") (pintype "passive"))
      (node (ref "C12") (pin "2") (pinfunction "2_2") (pintype "passive"))
      (node (ref "C13") (pin "2") (pinfunction "2_2") (pintype "passive"))
      (node (ref "C14") (pin "2") (pinfunction "2_2") (pintype "passive"))
      (node (ref "C15") (pin "2") (pinfunction "2_2") (pintype "passive"))
      (node (ref "C2") (pin "-") (pinfunction "-_-") (pintype "passive"))
      (node (ref "C3") (pin "-") (pinfunction "-_-") (pintype "passive"))
      (node (ref "C4") (pin "2") (pinfunction "2_2") (pintype "passive"))
      (node (ref "C5") (pin "2") (pinfunction "2_2") (pintype "passive"))
      (node (ref "C6") (pin "2") (pinfunction "2_2") (pintype "passive"))
      (node (ref "C7") (pin "2") (pinfunction "2_2") (pintype "passive"))
      (node (ref "C8") (pin "2") (pinfunction "2_2") (pintype "passive"))
      (node (ref "C9") (pin "2") (pinfunction "2_2") (pintype "passive"))
      (node (ref "E11") (pin "7") (pinfunction "G_7") (pintype "input"))
      (node (ref "E16") (pin "7") (pinfunction "G_7") (pintype "input"))
      (node (ref "E19") (pin "1") (pinfunction "1G_1") (pintype "input"))
      (node (ref "E19") (pin "15") (pinfunction "2G_15") (pintype "input"))
      (node (ref "E20") (pin "13") (pinfunction "S_13") (pintype "input"))
      (node (ref "E21") (pin "7") (pinfunction "G_7") (pintype "input"))
      (node (ref "E23") (pin "7") (pinfunction "G_7") (pintype "input"))
      (node (ref "E24") (pin "13") (pinfunction "S_13") (pintype "input"))
      (node (ref "E25") (pin "13") (pinfunction "S_13") (pintype "input"))
      (node (ref "E28") (pin "7") (pinfunction "G_7") (pintype "input"))
      (node (ref "E29") (pin "13") (pinfunction "S_13") (pintype "input"))
      (node (ref "E3") (pin "13") (pinfunction "S_13") (pintype "input"))
      (node (ref "E30") (pin "1") (pinfunction "1G_1") (pintype "input"))
      (node (ref "E30") (pin "15") (pinfunction "2G_15") (pintype "input"))
      (node (ref "E33") (pin "7") (pinfunction "G_7") (pintype "input"))
      (node (ref "E38") (pin "7") (pinfunction "G_7") (pintype "input"))
      (node (ref "E4") (pin "13") (pinfunction "S_13") (pintype "input"))
      (node (ref "E41") (pin "1") (pinfunction "1G_1") (pintype "input"))
      (node (ref "E41") (pin "15") (pinfunction "2G_15") (pintype "input"))
      (node (ref "E42") (pin "13") (pinfunction "S_13") (pintype "input"))
      (node (ref "E43") (pin "7") (pinfunction "G_7") (pintype "input"))
      (node (ref "E46") (pin "13") (pinfunction "S_13") (pintype "input"))
      (node (ref "E47") (pin "13") (pinfunction "S_13") (pintype "input"))
      (node (ref "E48") (pin "7") (pinfunction "G_7") (pintype "input"))
      (node (ref "E50") (pin "13") (pinfunction "S_13") (pintype "input"))
      (node (ref "E51") (pin "1") (pinfunction "1G_1") (pintype "input"))
      (node (ref "E51") (pin "15") (pinfunction "2G_15") (pintype "input"))
      (node (ref "E53") (pin "7") (pinfunction "G_7") (pintype "input"))
      (node (ref "E55") (pin "13") (pinfunction "S_13") (pintype "input"))
      (node (ref "E58") (pin "7") (pinfunction "G_7") (pintype "input"))
      (node (ref "E6") (pin "7") (pinfunction "G_7") (pintype "input"))
      (node (ref "E62") (pin "1") (pinfunction "1G_1") (pintype "input"))
      (node (ref "E62") (pin "15") (pinfunction "2G_15") (pintype "input"))
      (node (ref "E63") (pin "11") (pinfunction "I_11") (pintype "input"))
      (node (ref "E63") (pin "5") (pinfunction "I_5") (pintype "input"))
      (node (ref "E64") (pin "1") (pinfunction "I_1") (pintype "input"))
      (node (ref "E8") (pin "13") (pinfunction "S_13") (pintype "input"))
      (node (ref "E9") (pin "1") (pinfunction "1G_1") (pintype "input"))
      (node (ref "E9") (pin "15") (pinfunction "2G_15") (pintype "input"))
      (node (ref "U$2") (pin "AC2") (pinfunction "1_AC2") (pintype "bidirectional"))
      (node (ref "U$2") (pin "AF1") (pinfunction "1_AF1") (pintype "bidirectional"))
      (node (ref "U$2") (pin "AF2") (pinfunction "1_AF2") (pintype "bidirectional"))
      (node (ref "U$2") (pin "AN1") (pinfunction "1_AN1") (pintype "bidirectional"))
      (node (ref "U$2") (pin "AN2") (pinfunction "1_AN2") (pintype "bidirectional"))
      (node (ref "U$2") (pin "AT1") (pinfunction "1_AT1") (pintype "bidirectional"))
      (node (ref "U$2") (pin "AT2") (pinfunction "1_AT2") (pintype "bidirectional"))
      (node (ref "U$2") (pin "BC1") (pinfunction "1_BC1") (pintype "bidirectional"))
      (node (ref "U$2") (pin "BC2") (pinfunction "1_BC2") (pintype "bidirectional"))
      (node (ref "U$2") (pin "BF1") (pinfunction "1_BF1") (pintype "bidirectional"))
      (node (ref "U$2") (pin "BF2") (pinfunction "1_BF2") (pintype "bidirectional"))
      (node (ref "U$2") (pin "BN1") (pinfunction "1_BN1") (pintype "bidirectional"))
      (node (ref "U$2") (pin "BN2") (pinfunction "1_BN2") (pintype "bidirectional"))
      (node (ref "U$2") (pin "BT1") (pinfunction "1_BT1") (pintype "bidirectional"))
      (node (ref "U$2") (pin "BT2") (pinfunction "1_BT2") (pintype "bidirectional"))
      (node (ref "U$2") (pin "CC1") (pinfunction "1_CC1") (pintype "bidirectional"))
      (node (ref "U$2") (pin "CF1") (pinfunction "1_CF1") (pintype "bidirectional"))
      (node (ref "U$2") (pin "CF2") (pinfunction "1_CF2") (pintype "bidirectional"))
      (node (ref "U$2") (pin "CN1") (pinfunction "1_CN1") (pintype "bidirectional"))
      (node (ref "U$2") (pin "CN2") (pinfunction "1_CN2") (pintype "bidirectional"))
      (node (ref "U$2") (pin "CT1") (pinfunction "1_CT1") (pintype "bidirectional"))
      (node (ref "U$2") (pin "CT2") (pinfunction "1_CT2") (pintype "bidirectional"))
      (node (ref "U$2") (pin "DC1") (pinfunction "1_DC1") (pintype "bidirectional"))
      (node (ref "U$2") (pin "DC2") (pinfunction "1_DC2") (pintype "bidirectional"))
      (node (ref "U$2") (pin "DF1") (pinfunction "1_DF1") (pintype "bidirectional"))
      (node (ref "U$2") (pin "DF2") (pinfunction "1_DF2") (pintype "bidirectional"))
      (node (ref "U$2") (pin "DN2") (pinfunction "1_DN2") (pintype "bidirectional"))
      (node (ref "U$2") (pin "DT2") (pinfunction "1_DT2") (pintype "bidirectional"))
    )
    (net (code "46") (name "INIT") (class "Default")
      (node (ref "E63") (pin "13") (pinfunction "I_13") (pintype "input"))
      (node (ref "U$2") (pin "CR1") (pinfunction "1_CR1") (pintype "bidirectional"))
    )
    (net (code "47") (name "LEFT") (class "Default")
      (node (ref "E11") (pin "10") (pinfunction "B_10") (pintype "input"))
      (node (ref "E16") (pin "10") (pinfunction "B_10") (pintype "input"))
      (node (ref "E21") (pin "10") (pinfunction "B_10") (pintype "input"))
      (node (ref "E23") (pin "10") (pinfunction "B_10") (pintype "input"))
      (node (ref "E28") (pin "10") (pinfunction "B_10") (pintype "input"))
      (node (ref "E33") (pin "10") (pinfunction "B_10") (pintype "input"))
      (node (ref "E38") (pin "10") (pinfunction "B_10") (pintype "input"))
      (node (ref "E43") (pin "10") (pinfunction "B_10") (pintype "input"))
      (node (ref "E48") (pin "10") (pinfunction "B_10") (pintype "input"))
      (node (ref "E53") (pin "10") (pinfunction "B_10") (pintype "input"))
      (node (ref "E58") (pin "10") (pinfunction "B_10") (pintype "input"))
      (node (ref "E6") (pin "10") (pinfunction "B_10") (pintype "input"))
      (node (ref "E64") (pin "10") (pinfunction "O_10") (pintype "output"))
    )
    (net (code "48") (name "MB00") (class "Default")
      (node (ref "E13") (pin "1") (pinfunction "I0_1") (pintype "input"))
      (node (ref "E2") (pin "9") (pinfunction "I1_9") (pintype "input"))
      (node (ref "E3") (pin "11") (pinfunction "Q3_11") (pintype "output"))
    )
    (net (code "49") (name "MB01") (class "Default")
      (node (ref "E13") (pin "5") (pinfunction "I1_5") (pintype "input"))
      (node (ref "E2") (pin "12") (pinfunction "I1_12") (pintype "input"))
      (node (ref "E3") (pin "9") (pinfunction "Q2_9") (pintype "output"))
    )
    (net (code "50") (name "MB02") (class "Default")
      (node (ref "E13") (pin "12") (pinfunction "I0_12") (pintype "input"))
      (node (ref "E2") (pin "6") (pinfunction "I1_6") (pintype "input"))
      (node (ref "E3") (pin "5") (pinfunction "Q0_5") (pintype "output"))
    )
    (net (code "51") (name "MB03") (class "Default")
      (node (ref "E13") (pin "9") (pinfunction "I0_9") (pintype "input"))
      (node (ref "E2") (pin "2") (pinfunction "I0_2") (pintype "input"))
      (node (ref "E3") (pin "7") (pinfunction "Q1_7") (pintype "output"))
    )
    (net (code "52") (name "MB04") (class "Default")
      (node (ref "E24") (pin "11") (pinfunction "Q3_11") (pintype "output"))
      (node (ref "E27") (pin "9") (pinfunction "I1_9") (pintype "input"))
      (node (ref "E35") (pin "1") (pinfunction "I0_1") (pintype "input"))
    )
    (net (code "53") (name "MB05") (class "Default")
      (node (ref "E24") (pin "9") (pinfunction "Q2_9") (pintype "output"))
      (node (ref "E27") (pin "12") (pinfunction "I1_12") (pintype "input"))
      (node (ref "E35") (pin "5") (pinfunction "I1_5") (pintype "input"))
    )
    (net (code "54") (name "MB06") (class "Default")
      (node (ref "E24") (pin "5") (pinfunction "Q0_5") (pintype "output"))
      (node (ref "E27") (pin "6") (pinfunction "I1_6") (pintype "input"))
      (node (ref "E35") (pin "12") (pinfunction "I0_12") (pintype "input"))
    )
    (net (code "55") (name "MB07") (class "Default")
      (node (ref "E24") (pin "7") (pinfunction "Q1_7") (pintype "output"))
      (node (ref "E27") (pin "2") (pinfunction "I0_2") (pintype "input"))
      (node (ref "E35") (pin "9") (pinfunction "I0_9") (pintype "input"))
    )
    (net (code "56") (name "MB08") (class "Default")
      (node (ref "E49") (pin "8") (pinfunction "I0_8") (pintype "input"))
      (node (ref "E50") (pin "11") (pinfunction "Q3_11") (pintype "output"))
      (node (ref "E61") (pin "1") (pinfunction "I0_1") (pintype "input"))
    )
    (net (code "57") (name "MB09") (class "Default")
      (node (ref "E49") (pin "11") (pinfunction "I0_11") (pintype "input"))
      (node (ref "E50") (pin "9") (pinfunction "Q2_9") (pintype "output"))
      (node (ref "E61") (pin "4") (pinfunction "I0_4") (pintype "input"))
    )
    (net (code "58") (name "MB10") (class "Default")
      (node (ref "E49") (pin "6") (pinfunction "I1_6") (pintype "input"))
      (node (ref "E50") (pin "5") (pinfunction "Q0_5") (pintype "output"))
      (node (ref "E61") (pin "13") (pinfunction "I1_13") (pintype "input"))
    )
    (net (code "59") (name "MB11") (class "Default")
      (node (ref "E49") (pin "2") (pinfunction "I0_2") (pintype "input"))
      (node (ref "E50") (pin "7") (pinfunction "Q1_7") (pintype "output"))
      (node (ref "E61") (pin "10") (pinfunction "I1_10") (pintype "input"))
    )
    (net (code "60") (name "Net-(E1A-I1)") (class "Default")
      (node (ref "E1") (pin "11") (pinfunction "I0_11") (pintype "input"))
      (node (ref "E1") (pin "3") (pinfunction "I1_3") (pintype "input"))
      (node (ref "E1") (pin "5") (pinfunction "I0_5") (pintype "input"))
      (node (ref "E1") (pin "8") (pinfunction "I0_8") (pintype "input"))
      (node (ref "E22") (pin "11") (pinfunction "I0_11") (pintype "input"))
      (node (ref "E22") (pin "3") (pinfunction "I1_3") (pintype "input"))
      (node (ref "E22") (pin "5") (pinfunction "I0_5") (pintype "input"))
      (node (ref "E22") (pin "8") (pinfunction "I0_8") (pintype "input"))
      (node (ref "E44") (pin "11") (pinfunction "I0_11") (pintype "input"))
      (node (ref "E44") (pin "3") (pinfunction "I1_3") (pintype "input"))
      (node (ref "E44") (pin "5") (pinfunction "I0_5") (pintype "input"))
      (node (ref "E44") (pin "9") (pinfunction "I1_9") (pintype "input"))
      (node (ref "E64") (pin "6") (pinfunction "O_6") (pintype "output"))
    )
    (net (code "61") (name "Net-(E12A-F0)") (class "Default")
      (node (ref "E12") (pin "3") (pinfunction "F0_3") (pintype "output"))
      (node (ref "E17") (pin "2") (pinfunction "I1_2") (pintype "input"))
    )
    (net (code "62") (name "Net-(E12A-F1)") (class "Default")
      (node (ref "E12") (pin "4") (pinfunction "F1_4") (pintype "output"))
      (node (ref "E17") (pin "3") (pinfunction "I0_3") (pintype "input"))
    )
    (net (code "63") (name "Net-(E12A-F2)") (class "Default")
      (node (ref "E12") (pin "12") (pinfunction "F2_12") (pintype "output"))
      (node (ref "E17") (pin "14") (pinfunction "I3_14") (pintype "input"))
    )
    (net (code "64") (name "Net-(E12A-F3)") (class "Default")
      (node (ref "E12") (pin "13") (pinfunction "F3_13") (pintype "output"))
      (node (ref "E17") (pin "15") (pinfunction "I2_15") (pintype "input"))
    )
    (net (code "65") (name "Net-(E14A-A0)") (class "Default")
      (node (ref "E14") (pin "1") (pinfunction "A0_1") (pintype "input"))
      (node (ref "E14") (pin "2") (pinfunction "B0_2") (pintype "input"))
      (node (ref "E19") (pin "7") (pinfunction "1Y_7") (pintype "output"))
    )
    (net (code "66") (name "Net-(E14A-A1)") (class "Default")
      (node (ref "E14") (pin "5") (pinfunction "B1_5") (pintype "input"))
      (node (ref "E14") (pin "6") (pinfunction "A1_6") (pintype "input"))
      (node (ref "E19") (pin "9") (pinfunction "2Y_9") (pintype "output"))
    )
    (net (code "67") (name "Net-(E14A-A2)") (class "Default")
      (node (ref "E14") (pin "10") (pinfunction "A2_10") (pintype "input"))
      (node (ref "E14") (pin "11") (pinfunction "B2_11") (pintype "input"))
      (node (ref "E9") (pin "9") (pinfunction "2Y_9") (pintype "output"))
    )
    (net (code "68") (name "Net-(E14A-A3)") (class "Default")
      (node (ref "E14") (pin "14") (pinfunction "B3_14") (pintype "input"))
      (node (ref "E14") (pin "15") (pinfunction "A3_15") (pintype "input"))
      (node (ref "E9") (pin "7") (pinfunction "1Y_7") (pintype "output"))
    )
    (net (code "69") (name "Net-(E18A-I0)") (class "Default")
      (node (ref "E18") (pin "1") (pinfunction "I0_1") (pintype "input"))
      (node (ref "E40") (pin "10") (pinfunction "O_10") (pintype "output"))
    )
    (net (code "70") (name "Net-(E18A-I1)") (class "Default")
      (node (ref "E18") (pin "2") (pinfunction "I1_2") (pintype "input"))
      (node (ref "E40") (pin "13") (pinfunction "O_13") (pintype "output"))
    )
    (net (code "71") (name "Net-(E18A-I2)") (class "Default")
      (node (ref "E18") (pin "4") (pinfunction "I2_4") (pintype "input"))
      (node (ref "E40") (pin "1") (pinfunction "O_1") (pintype "output"))
    )
    (net (code "72") (name "Net-(E18A-I3)") (class "Default")
      (node (ref "E18") (pin "5") (pinfunction "I3_5") (pintype "input"))
      (node (ref "E40") (pin "4") (pinfunction "O_4") (pintype "output"))
    )
    (net (code "73") (name "Net-(E27A-I1)") (class "Default")
      (node (ref "E2") (pin "11") (pinfunction "I0_11") (pintype "input"))
      (node (ref "E2") (pin "3") (pinfunction "I1_3") (pintype "input"))
      (node (ref "E2") (pin "5") (pinfunction "I0_5") (pintype "input"))
      (node (ref "E2") (pin "8") (pinfunction "I0_8") (pintype "input"))
      (node (ref "E27") (pin "11") (pinfunction "I0_11") (pintype "input"))
      (node (ref "E27") (pin "3") (pinfunction "I1_3") (pintype "input"))
      (node (ref "E27") (pin "5") (pinfunction "I0_5") (pintype "input"))
      (node (ref "E27") (pin "8") (pinfunction "I0_8") (pintype "input"))
      (node (ref "E49") (pin "12") (pinfunction "I1_12") (pintype "input"))
      (node (ref "E49") (pin "3") (pinfunction "I1_3") (pintype "input"))
      (node (ref "E49") (pin "5") (pinfunction "I0_5") (pintype "input"))
      (node (ref "E49") (pin "9") (pinfunction "I1_9") (pintype "input"))
      (node (ref "E63") (pin "4") (pinfunction "O_4") (pintype "output"))
    )
    (net (code "74") (name "Net-(E30A-1Y)") (class "Default")
      (node (ref "E30") (pin "7") (pinfunction "1Y_7") (pintype "output"))
      (node (ref "E36") (pin "14") (pinfunction "B3_14") (pintype "input"))
      (node (ref "E36") (pin "15") (pinfunction "A3_15") (pintype "input"))
    )
    (net (code "75") (name "Net-(E30A-2Y)") (class "Default")
      (node (ref "E30") (pin "9") (pinfunction "2Y_9") (pintype "output"))
      (node (ref "E36") (pin "10") (pinfunction "A2_10") (pintype "input"))
      (node (ref "E36") (pin "11") (pinfunction "B2_11") (pintype "input"))
    )
    (net (code "76") (name "Net-(E34A-F0)") (class "Default")
      (node (ref "E34") (pin "3") (pinfunction "F0_3") (pintype "output"))
      (node (ref "E39") (pin "2") (pinfunction "I1_2") (pintype "input"))
    )
    (net (code "77") (name "Net-(E34A-F1)") (class "Default")
      (node (ref "E34") (pin "4") (pinfunction "F1_4") (pintype "output"))
      (node (ref "E39") (pin "3") (pinfunction "I0_3") (pintype "input"))
    )
    (net (code "78") (name "Net-(E34A-F2)") (class "Default")
      (node (ref "E34") (pin "12") (pinfunction "F2_12") (pintype "output"))
      (node (ref "E39") (pin "14") (pinfunction "I3_14") (pintype "input"))
    )
    (net (code "79") (name "Net-(E34A-F3)") (class "Default")
      (node (ref "E34") (pin "13") (pinfunction "F3_13") (pintype "output"))
      (node (ref "E39") (pin "15") (pinfunction "I2_15") (pintype "input"))
    )
    (net (code "80") (name "Net-(E36A-A0)") (class "Default")
      (node (ref "E36") (pin "1") (pinfunction "A0_1") (pintype "input"))
      (node (ref "E36") (pin "2") (pinfunction "B0_2") (pintype "input"))
      (node (ref "E41") (pin "7") (pinfunction "1Y_7") (pintype "output"))
    )
    (net (code "81") (name "Net-(E36A-A1)") (class "Default")
      (node (ref "E36") (pin "5") (pinfunction "B1_5") (pintype "input"))
      (node (ref "E36") (pin "6") (pinfunction "A1_6") (pintype "input"))
      (node (ref "E41") (pin "9") (pinfunction "2Y_9") (pintype "output"))
    )
    (net (code "82") (name "Net-(E51A-1Y)") (class "Default")
      (node (ref "E51") (pin "7") (pinfunction "1Y_7") (pintype "output"))
      (node (ref "E56") (pin "10") (pinfunction "A2_10") (pintype "input"))
      (node (ref "E56") (pin "11") (pinfunction "B2_11") (pintype "input"))
    )
    (net (code "83") (name "Net-(E51A-2Y)") (class "Default")
      (node (ref "E51") (pin "9") (pinfunction "2Y_9") (pintype "output"))
      (node (ref "E56") (pin "14") (pinfunction "B3_14") (pintype "input"))
      (node (ref "E56") (pin "15") (pinfunction "A3_15") (pintype "input"))
    )
    (net (code "84") (name "Net-(E54A-I0)") (class "Default")
      (node (ref "E54") (pin "3") (pinfunction "I0_3") (pintype "input"))
      (node (ref "E59") (pin "12") (pinfunction "F2_12") (pintype "output"))
    )
    (net (code "85") (name "Net-(E54A-I1)") (class "Default")
      (node (ref "E54") (pin "2") (pinfunction "I1_2") (pintype "input"))
      (node (ref "E59") (pin "13") (pinfunction "F3_13") (pintype "output"))
    )
    (net (code "86") (name "Net-(E54A-I2)") (class "Default")
      (node (ref "E54") (pin "15") (pinfunction "I2_15") (pintype "input"))
      (node (ref "E59") (pin "3") (pinfunction "F0_3") (pintype "output"))
    )
    (net (code "87") (name "Net-(E54A-I3)") (class "Default")
      (node (ref "E54") (pin "14") (pinfunction "I3_14") (pintype "input"))
      (node (ref "E59") (pin "4") (pinfunction "F1_4") (pintype "output"))
    )
    (net (code "88") (name "Net-(E56A-A0)") (class "Default")
      (node (ref "E56") (pin "1") (pinfunction "A0_1") (pintype "input"))
      (node (ref "E56") (pin "2") (pinfunction "B0_2") (pintype "input"))
      (node (ref "E62") (pin "9") (pinfunction "2Y_9") (pintype "output"))
    )
    (net (code "89") (name "Net-(E56A-A1)") (class "Default")
      (node (ref "E56") (pin "5") (pinfunction "B1_5") (pintype "input"))
      (node (ref "E56") (pin "6") (pinfunction "A1_6") (pintype "input"))
      (node (ref "E62") (pin "7") (pinfunction "1Y_7") (pintype "output"))
    )
    (net (code "90") (name "Net-(E63A-O)") (class "Default")
      (node (ref "E63") (pin "2") (pinfunction "O_2") (pintype "output"))
      (node (ref "E63") (pin "3") (pinfunction "I_3") (pintype "input"))
    )
    (net (code "91") (name "PAGEZ") (class "Default")
      (node (ref "E26") (pin "7") (pinfunction "S1_7") (pintype "input"))
      (node (ref "E26") (pin "9") (pinfunction "S0_9") (pintype "input"))
      (node (ref "E5") (pin "7") (pinfunction "S1_7") (pintype "input"))
      (node (ref "E5") (pin "9") (pinfunction "S0_9") (pintype "input"))
      (node (ref "H") (pin "C1") (pinfunction "P_C1") (pintype "passive"))
    )
    (net (code "92") (name "REGBUS00") (class "Default")
      (node (ref "E3") (pin "14") (pinfunction "I3_14") (pintype "input"))
      (node (ref "E4") (pin "15") (pinfunction "I2_15") (pintype "input"))
      (node (ref "E6") (pin "6") (pinfunction "W_6") (pintype "output"))
      (node (ref "E8") (pin "14") (pinfunction "I3_14") (pintype "input"))
    )
    (net (code "93") (name "REGBUS01") (class "Default")
      (node (ref "E11") (pin "6") (pinfunction "W_6") (pintype "output"))
      (node (ref "E3") (pin "15") (pinfunction "I2_15") (pintype "input"))
      (node (ref "E4") (pin "14") (pinfunction "I3_14") (pintype "input"))
      (node (ref "E8") (pin "15") (pinfunction "I2_15") (pintype "input"))
    )
    (net (code "94") (name "REGBUS02") (class "Default")
      (node (ref "E16") (pin "6") (pinfunction "W_6") (pintype "output"))
      (node (ref "E3") (pin "3") (pinfunction "I0_3") (pintype "input"))
      (node (ref "E4") (pin "2") (pinfunction "I1_2") (pintype "input"))
      (node (ref "E8") (pin "3") (pinfunction "I0_3") (pintype "input"))
    )
    (net (code "95") (name "REGBUS03") (class "Default")
      (node (ref "E21") (pin "6") (pinfunction "W_6") (pintype "output"))
      (node (ref "E3") (pin "2") (pinfunction "I1_2") (pintype "input"))
      (node (ref "E4") (pin "3") (pinfunction "I0_3") (pintype "input"))
      (node (ref "E8") (pin "2") (pinfunction "I1_2") (pintype "input"))
    )
    (net (code "96") (name "REGBUS04") (class "Default")
      (node (ref "E23") (pin "6") (pinfunction "W_6") (pintype "output"))
      (node (ref "E24") (pin "14") (pinfunction "I3_14") (pintype "input"))
      (node (ref "E25") (pin "15") (pinfunction "I2_15") (pintype "input"))
      (node (ref "E29") (pin "14") (pinfunction "I3_14") (pintype "input"))
    )
    (net (code "97") (name "REGBUS05") (class "Default")
      (node (ref "E24") (pin "15") (pinfunction "I2_15") (pintype "input"))
      (node (ref "E25") (pin "14") (pinfunction "I3_14") (pintype "input"))
      (node (ref "E28") (pin "6") (pinfunction "W_6") (pintype "output"))
      (node (ref "E29") (pin "15") (pinfunction "I2_15") (pintype "input"))
    )
    (net (code "98") (name "REGBUS06") (class "Default")
      (node (ref "E24") (pin "3") (pinfunction "I0_3") (pintype "input"))
      (node (ref "E25") (pin "2") (pinfunction "I1_2") (pintype "input"))
      (node (ref "E29") (pin "3") (pinfunction "I0_3") (pintype "input"))
      (node (ref "E33") (pin "6") (pinfunction "W_6") (pintype "output"))
    )
    (net (code "99") (name "REGBUS07") (class "Default")
      (node (ref "E24") (pin "2") (pinfunction "I1_2") (pintype "input"))
      (node (ref "E25") (pin "3") (pinfunction "I0_3") (pintype "input"))
      (node (ref "E29") (pin "2") (pinfunction "I1_2") (pintype "input"))
      (node (ref "E38") (pin "6") (pinfunction "W_6") (pintype "output"))
    )
    (net (code "100") (name "REGBUS08") (class "Default")
      (node (ref "E43") (pin "6") (pinfunction "W_6") (pintype "output"))
      (node (ref "E46") (pin "15") (pinfunction "I2_15") (pintype "input"))
      (node (ref "E50") (pin "14") (pinfunction "I3_14") (pintype "input"))
      (node (ref "E55") (pin "14") (pinfunction "I3_14") (pintype "input"))
    )
    (net (code "101") (name "REGBUS09") (class "Default")
      (node (ref "E46") (pin "14") (pinfunction "I3_14") (pintype "input"))
      (node (ref "E48") (pin "6") (pinfunction "W_6") (pintype "output"))
      (node (ref "E50") (pin "15") (pinfunction "I2_15") (pintype "input"))
      (node (ref "E55") (pin "15") (pinfunction "I2_15") (pintype "input"))
    )
    (net (code "102") (name "REGBUS10") (class "Default")
      (node (ref "E46") (pin "3") (pinfunction "I0_3") (pintype "input"))
      (node (ref "E50") (pin "3") (pinfunction "I0_3") (pintype "input"))
      (node (ref "E53") (pin "6") (pinfunction "W_6") (pintype "output"))
      (node (ref "E55") (pin "3") (pinfunction "I0_3") (pintype "input"))
    )
    (net (code "103") (name "REGBUS11") (class "Default")
      (node (ref "E46") (pin "2") (pinfunction "I1_2") (pintype "input"))
      (node (ref "E50") (pin "2") (pinfunction "I1_2") (pintype "input"))
      (node (ref "E55") (pin "2") (pinfunction "I1_2") (pintype "input"))
      (node (ref "E58") (pin "6") (pinfunction "W_6") (pintype "output"))
    )
    (net (code "104") (name "RIGHT") (class "Default")
      (node (ref "E11") (pin "9") (pinfunction "C_9") (pintype "input"))
      (node (ref "E16") (pin "9") (pinfunction "C_9") (pintype "input"))
      (node (ref "E21") (pin "9") (pinfunction "C_9") (pintype "input"))
      (node (ref "E23") (pin "9") (pinfunction "C_9") (pintype "input"))
      (node (ref "E28") (pin "9") (pinfunction "C_9") (pintype "input"))
      (node (ref "E33") (pin "9") (pinfunction "C_9") (pintype "input"))
      (node (ref "E38") (pin "9") (pinfunction "C_9") (pintype "input"))
      (node (ref "E43") (pin "9") (pinfunction "C_9") (pintype "input"))
      (node (ref "E48") (pin "9") (pinfunction "C_9") (pintype "input"))
      (node (ref "E53") (pin "9") (pinfunction "C_9") (pintype "input"))
      (node (ref "E58") (pin "9") (pinfunction "C_9") (pintype "input"))
      (node (ref "E6") (pin "9") (pinfunction "C_9") (pintype "input"))
      (node (ref "E64") (pin "8") (pinfunction "O_8") (pintype "output"))
    )
    (net (code "105") (name "RIGHT2") (class "Default")
      (node (ref "E17") (pin "13") (pinfunction "S_13") (pintype "input"))
      (node (ref "E39") (pin "13") (pinfunction "S_13") (pintype "input"))
      (node (ref "E54") (pin "13") (pinfunction "S_13") (pintype "input"))
      (node (ref "E63") (pin "8") (pinfunction "O_8") (pintype "output"))
    )
    (net (code "106") (name "TWICE") (class "Default")
      (node (ref "E11") (pin "11") (pinfunction "A_11") (pintype "input"))
      (node (ref "E16") (pin "11") (pinfunction "A_11") (pintype "input"))
      (node (ref "E21") (pin "11") (pinfunction "A_11") (pintype "input"))
      (node (ref "E23") (pin "11") (pinfunction "A_11") (pintype "input"))
      (node (ref "E28") (pin "11") (pinfunction "A_11") (pintype "input"))
      (node (ref "E33") (pin "11") (pinfunction "A_11") (pintype "input"))
      (node (ref "E38") (pin "11") (pinfunction "A_11") (pintype "input"))
      (node (ref "E43") (pin "11") (pinfunction "A_11") (pintype "input"))
      (node (ref "E48") (pin "11") (pinfunction "A_11") (pintype "input"))
      (node (ref "E53") (pin "11") (pinfunction "A_11") (pintype "input"))
      (node (ref "E58") (pin "11") (pinfunction "A_11") (pintype "input"))
      (node (ref "E6") (pin "11") (pinfunction "A_11") (pintype "input"))
      (node (ref "E64") (pin "12") (pinfunction "O_12") (pintype "output"))
    )
    (net (code "107") (name "VCC") (class "Default")
      (node (ref "C1") (pin "+") (pinfunction "+_+") (pintype "passive"))
      (node (ref "C10") (pin "1") (pinfunction "1_1") (pintype "passive"))
      (node (ref "C11") (pin "1") (pinfunction "1_1") (pintype "passive"))
      (node (ref "C12") (pin "1") (pinfunction "1_1") (pintype "passive"))
      (node (ref "C13") (pin "1") (pinfunction "1_1") (pintype "passive"))
      (node (ref "C14") (pin "1") (pinfunction "1_1") (pintype "passive"))
      (node (ref "C2") (pin "+") (pinfunction "+_+") (pintype "passive"))
      (node (ref "C3") (pin "+") (pinfunction "+_+") (pintype "passive"))
      (node (ref "C4") (pin "1") (pinfunction "1_1") (pintype "passive"))
      (node (ref "C5") (pin "1") (pinfunction "1_1") (pintype "passive"))
      (node (ref "C6") (pin "1") (pinfunction "1_1") (pintype "passive"))
      (node (ref "C7") (pin "1") (pinfunction "1_1") (pintype "passive"))
      (node (ref "C8") (pin "1") (pinfunction "1_1") (pintype "passive"))
      (node (ref "C9") (pin "1") (pinfunction "1_1") (pintype "passive"))
      (node (ref "E26") (pin "15") (pinfunction "A3_15") (pintype "input"))
      (node (ref "E5") (pin "10") (pinfunction "A2_10") (pintype "input"))
      (node (ref "E5") (pin "15") (pinfunction "A3_15") (pintype "input"))
      (node (ref "R1") (pin "2") (pinfunction "2_2") (pintype "passive"))
      (node (ref "U$2") (pin "AA2") (pinfunction "1_AA2") (pintype "bidirectional"))
      (node (ref "U$2") (pin "BA2") (pinfunction "1_BA2") (pintype "bidirectional"))
      (node (ref "U$2") (pin "CA2") (pinfunction "1_CA2") (pintype "bidirectional"))
    )
    (net (code "108") (name "unconnected-(E3A-D-Pad4)") (class "Default")
      (node (ref "E3") (pin "4") (pinfunction "D_4") (pintype "input"))
    )
    (net (code "109") (name "unconnected-(E3A-Q4-Pad12)") (class "Default")
      (node (ref "E3") (pin "12") (pinfunction "Q4_12") (pintype "output"))
    )
    (net (code "110") (name "unconnected-(E4A-D-Pad4)") (class "Default")
      (node (ref "E4") (pin "4") (pinfunction "D_4") (pintype "input"))
    )
    (net (code "111") (name "unconnected-(E4A-Q4-Pad12)") (class "Default")
      (node (ref "E4") (pin "12") (pinfunction "Q4_12") (pintype "output"))
    )
    (net (code "112") (name "unconnected-(E5A-A0-Pad1)") (class "Default")
      (node (ref "E5") (pin "1") (pinfunction "A0_1") (pintype "input"))
    )
    (net (code "113") (name "unconnected-(E5A-A1-Pad6)") (class "Default")
      (node (ref "E5") (pin "6") (pinfunction "A1_6") (pintype "input"))
    )
    (net (code "114") (name "unconnected-(E8A-D-Pad4)") (class "Default")
      (node (ref "E8") (pin "4") (pinfunction "D_4") (pintype "input"))
    )
    (net (code "115") (name "unconnected-(E8A-Q4-Pad12)") (class "Default")
      (node (ref "E8") (pin "12") (pinfunction "Q4_12") (pintype "output"))
    )
    (net (code "116") (name "unconnected-(E17A-Q4-Pad12)") (class "Default")
      (node (ref "E17") (pin "12") (pinfunction "Q4_12") (pintype "output"))
    )
    (net (code "117") (name "unconnected-(E20A-D-Pad4)") (class "Default")
      (node (ref "E20") (pin "4") (pinfunction "D_4") (pintype "input"))
    )
    (net (code "118") (name "unconnected-(E20A-Q4-Pad12)") (class "Default")
      (node (ref "E20") (pin "12") (pinfunction "Q4_12") (pintype "output"))
    )
    (net (code "119") (name "unconnected-(E24A-D-Pad4)") (class "Default")
      (node (ref "E24") (pin "4") (pinfunction "D_4") (pintype "input"))
    )
    (net (code "120") (name "unconnected-(E24A-Q4-Pad12)") (class "Default")
      (node (ref "E24") (pin "12") (pinfunction "Q4_12") (pintype "output"))
    )
    (net (code "121") (name "unconnected-(E25A-D-Pad4)") (class "Default")
      (node (ref "E25") (pin "4") (pinfunction "D_4") (pintype "input"))
    )
    (net (code "122") (name "unconnected-(E25A-Q4-Pad12)") (class "Default")
      (node (ref "E25") (pin "12") (pinfunction "Q4_12") (pintype "output"))
    )
    (net (code "123") (name "unconnected-(E26A-A0-Pad1)") (class "Default")
      (node (ref "E26") (pin "1") (pinfunction "A0_1") (pintype "input"))
    )
    (net (code "124") (name "unconnected-(E26A-A1-Pad6)") (class "Default")
      (node (ref "E26") (pin "6") (pinfunction "A1_6") (pintype "input"))
    )
    (net (code "125") (name "unconnected-(E26A-A2-Pad10)") (class "Default")
      (node (ref "E26") (pin "10") (pinfunction "A2_10") (pintype "input"))
    )
    (net (code "126") (name "unconnected-(E26A-B0-Pad2)") (class "Default")
      (node (ref "E26") (pin "2") (pinfunction "B0_2") (pintype "input"))
    )
    (net (code "127") (name "unconnected-(E26A-B1-Pad5)") (class "Default")
      (node (ref "E26") (pin "5") (pinfunction "B1_5") (pintype "input"))
    )
    (net (code "128") (name "unconnected-(E26A-B2-Pad11)") (class "Default")
      (node (ref "E26") (pin "11") (pinfunction "B2_11") (pintype "input"))
    )
    (net (code "129") (name "unconnected-(E26A-F0-Pad3)") (class "Default")
      (node (ref "E26") (pin "3") (pinfunction "F0_3") (pintype "output"))
    )
    (net (code "130") (name "unconnected-(E26A-F1-Pad4)") (class "Default")
      (node (ref "E26") (pin "4") (pinfunction "F1_4") (pintype "output"))
    )
    (net (code "131") (name "unconnected-(E26A-F2-Pad12)") (class "Default")
      (node (ref "E26") (pin "12") (pinfunction "F2_12") (pintype "output"))
    )
    (net (code "132") (name "unconnected-(E29A-D-Pad4)") (class "Default")
      (node (ref "E29") (pin "4") (pinfunction "D_4") (pintype "input"))
    )
    (net (code "133") (name "unconnected-(E29A-Q4-Pad12)") (class "Default")
      (node (ref "E29") (pin "12") (pinfunction "Q4_12") (pintype "output"))
    )
    (net (code "134") (name "unconnected-(E39A-Q4-Pad12)") (class "Default")
      (node (ref "E39") (pin "12") (pinfunction "Q4_12") (pintype "output"))
    )
    (net (code "135") (name "unconnected-(E42A-D-Pad4)") (class "Default")
      (node (ref "E42") (pin "4") (pinfunction "D_4") (pintype "input"))
    )
    (net (code "136") (name "unconnected-(E42A-Q4-Pad12)") (class "Default")
      (node (ref "E42") (pin "12") (pinfunction "Q4_12") (pintype "output"))
    )
    (net (code "137") (name "unconnected-(E46A-D-Pad4)") (class "Default")
      (node (ref "E46") (pin "4") (pinfunction "D_4") (pintype "input"))
    )
    (net (code "138") (name "unconnected-(E46A-Q4-Pad12)") (class "Default")
      (node (ref "E46") (pin "12") (pinfunction "Q4_12") (pintype "output"))
    )
    (net (code "139") (name "unconnected-(E47A-D-Pad4)") (class "Default")
      (node (ref "E47") (pin "4") (pinfunction "D_4") (pintype "input"))
    )
    (net (code "140") (name "unconnected-(E47A-Q4-Pad12)") (class "Default")
      (node (ref "E47") (pin "12") (pinfunction "Q4_12") (pintype "output"))
    )
    (net (code "141") (name "unconnected-(E50A-D-Pad4)") (class "Default")
      (node (ref "E50") (pin "4") (pinfunction "D_4") (pintype "input"))
    )
    (net (code "142") (name "unconnected-(E50A-Q4-Pad12)") (class "Default")
      (node (ref "E50") (pin "12") (pinfunction "Q4_12") (pintype "output"))
    )
    (net (code "143") (name "unconnected-(E54A-Q4-Pad12)") (class "Default")
      (node (ref "E54") (pin "12") (pinfunction "Q4_12") (pintype "output"))
    )
    (net (code "144") (name "unconnected-(E55A-D-Pad4)") (class "Default")
      (node (ref "E55") (pin "4") (pinfunction "D_4") (pintype "input"))
    )
    (net (code "145") (name "unconnected-(E55A-Q4-Pad12)") (class "Default")
      (node (ref "E55") (pin "12") (pinfunction "Q4_12") (pintype "output"))
    )
    (net (code "146") (name "~{A00}") (class "Default")
      (node (ref "E14") (pin "13") (pinfunction "F3_13") (pintype "output"))
      (node (ref "E15") (pin "16") (pinfunction "B4_16") (pintype "input"))
    )
    (net (code "147") (name "~{A01}") (class "Default")
      (node (ref "E14") (pin "12") (pinfunction "F2_12") (pintype "output"))
      (node (ref "E15") (pin "4") (pinfunction "B3_4") (pintype "input"))
    )
    (net (code "148") (name "~{A02}") (class "Default")
      (node (ref "E14") (pin "3") (pinfunction "F0_3") (pintype "output"))
      (node (ref "E15") (pin "8") (pinfunction "A2_8") (pintype "input"))
    )
    (net (code "149") (name "~{A03}") (class "Default")
      (node (ref "E14") (pin "4") (pinfunction "F1_4") (pintype "output"))
      (node (ref "E15") (pin "10") (pinfunction "A1_10") (pintype "input"))
    )
    (net (code "150") (name "~{A04}") (class "Default")
      (node (ref "E36") (pin "13") (pinfunction "F3_13") (pintype "output"))
      (node (ref "E37") (pin "16") (pinfunction "B4_16") (pintype "input"))
    )
    (net (code "151") (name "~{A05}") (class "Default")
      (node (ref "E36") (pin "12") (pinfunction "F2_12") (pintype "output"))
      (node (ref "E37") (pin "4") (pinfunction "B3_4") (pintype "input"))
    )
    (net (code "152") (name "~{A06}") (class "Default")
      (node (ref "E36") (pin "3") (pinfunction "F0_3") (pintype "output"))
      (node (ref "E37") (pin "8") (pinfunction "A2_8") (pintype "input"))
    )
    (net (code "153") (name "~{A07}") (class "Default")
      (node (ref "E36") (pin "4") (pinfunction "F1_4") (pintype "output"))
      (node (ref "E37") (pin "10") (pinfunction "A1_10") (pintype "input"))
    )
    (net (code "154") (name "~{A08}") (class "Default")
      (node (ref "E52") (pin "1") (pinfunction "A4_1") (pintype "input"))
      (node (ref "E56") (pin "12") (pinfunction "F2_12") (pintype "output"))
    )
    (net (code "155") (name "~{A09}") (class "Default")
      (node (ref "E52") (pin "4") (pinfunction "B3_4") (pintype "input"))
      (node (ref "E56") (pin "13") (pinfunction "F3_13") (pintype "output"))
    )
    (net (code "156") (name "~{A10}") (class "Default")
      (node (ref "E52") (pin "8") (pinfunction "A2_8") (pintype "input"))
      (node (ref "E56") (pin "4") (pinfunction "F1_4") (pintype "output"))
    )
    (net (code "157") (name "~{A11}") (class "Default")
      (node (ref "E52") (pin "10") (pinfunction "A1_10") (pintype "input"))
      (node (ref "E56") (pin "3") (pinfunction "F0_3") (pintype "output"))
    )
    (net (code "158") (name "~{AC2BUS}") (class "Default")
      (node (ref "E") (pin "T2") (pinfunction "P_T2") (pintype "passive"))
      (node (ref "E32") (pin "7") (pinfunction "S1_7") (pintype "input"))
      (node (ref "E60") (pin "7") (pinfunction "S1_7") (pintype "input"))
      (node (ref "E7") (pin "7") (pinfunction "S1_7") (pintype "input"))
    )
    (net (code "159") (name "~{AC04-11EQ0}") (class "Default")
      (node (ref "E") (pin "B1") (pinfunction "P_B1") (pintype "passive"))
      (node (ref "E18") (pin "6") (pinfunction "O_6") (pintype "output"))
    )
    (net (code "160") (name "~{AC_LOAD}") (class "Default")
      (node (ref "E") (pin "L1") (pinfunction "P_L1") (pintype "passive"))
      (node (ref "E29") (pin "6") (pinfunction "C_6") (pintype "input"))
      (node (ref "E55") (pin "6") (pinfunction "C_6") (pintype "input"))
      (node (ref "E8") (pin "6") (pinfunction "C_6") (pintype "input"))
    )
    (net (code "161") (name "~{AD00}") (class "Default")
      (node (ref "E11") (pin "15") (pinfunction "D4_15") (pintype "input"))
      (node (ref "E15") (pin "15") (pinfunction "S4_15") (pintype "output"))
      (node (ref "E16") (pin "14") (pinfunction "D5_14") (pintype "input"))
      (node (ref "E33") (pin "3") (pinfunction "D1_3") (pintype "input"))
      (node (ref "E58") (pin "1") (pinfunction "D3_1") (pintype "input"))
      (node (ref "E6") (pin "4") (pinfunction "D0_4") (pintype "input"))
      (node (ref "H") (pin "P1") (pinfunction "P_P1") (pintype "passive"))
    )
    (net (code "162") (name "~{AD01}") (class "Default")
      (node (ref "E11") (pin "4") (pinfunction "D0_4") (pintype "input"))
      (node (ref "E15") (pin "2") (pinfunction "S3_2") (pintype "output"))
      (node (ref "E16") (pin "15") (pinfunction "D4_15") (pintype "input"))
      (node (ref "E21") (pin "14") (pinfunction "D5_14") (pintype "input"))
      (node (ref "E38") (pin "3") (pinfunction "D1_3") (pintype "input"))
      (node (ref "E6") (pin "2") (pinfunction "D2_2") (pintype "input"))
      (node (ref "H") (pin "R1") (pinfunction "P_R1") (pintype "passive"))
    )
    (net (code "163") (name "~{AD02}") (class "Default")
      (node (ref "E11") (pin "2") (pinfunction "D2_2") (pintype "input"))
      (node (ref "E15") (pin "6") (pinfunction "S2_6") (pintype "output"))
      (node (ref "E16") (pin "4") (pinfunction "D0_4") (pintype "input"))
      (node (ref "E21") (pin "15") (pinfunction "D4_15") (pintype "input"))
      (node (ref "E23") (pin "14") (pinfunction "D5_14") (pintype "input"))
      (node (ref "E43") (pin "3") (pinfunction "D1_3") (pintype "input"))
      (node (ref "E6") (pin "1") (pinfunction "D3_1") (pintype "input"))
    )
    (net (code "164") (name "~{AD03}") (class "Default")
      (node (ref "E11") (pin "1") (pinfunction "D3_1") (pintype "input"))
      (node (ref "E15") (pin "9") (pinfunction "S1_9") (pintype "output"))
      (node (ref "E16") (pin "2") (pinfunction "D2_2") (pintype "input"))
      (node (ref "E21") (pin "4") (pinfunction "D0_4") (pintype "input"))
      (node (ref "E23") (pin "15") (pinfunction "D4_15") (pintype "input"))
      (node (ref "E28") (pin "14") (pinfunction "D5_14") (pintype "input"))
      (node (ref "E48") (pin "3") (pinfunction "D1_3") (pintype "input"))
    )
    (net (code "165") (name "~{AD04}") (class "Default")
      (node (ref "E16") (pin "1") (pinfunction "D3_1") (pintype "input"))
      (node (ref "E21") (pin "2") (pinfunction "D2_2") (pintype "input"))
      (node (ref "E23") (pin "4") (pinfunction "D0_4") (pintype "input"))
      (node (ref "E28") (pin "15") (pinfunction "D4_15") (pintype "input"))
      (node (ref "E33") (pin "14") (pinfunction "D5_14") (pintype "input"))
      (node (ref "E37") (pin "15") (pinfunction "S4_15") (pintype "output"))
      (node (ref "E53") (pin "3") (pinfunction "D1_3") (pintype "input"))
    )
    (net (code "166") (name "~{AD05}") (class "Default")
      (node (ref "E21") (pin "1") (pinfunction "D3_1") (pintype "input"))
      (node (ref "E23") (pin "2") (pinfunction "D2_2") (pintype "input"))
      (node (ref "E28") (pin "4") (pinfunction "D0_4") (pintype "input"))
      (node (ref "E33") (pin "15") (pinfunction "D4_15") (pintype "input"))
      (node (ref "E37") (pin "2") (pinfunction "S3_2") (pintype "output"))
      (node (ref "E38") (pin "14") (pinfunction "D5_14") (pintype "input"))
      (node (ref "E58") (pin "3") (pinfunction "D1_3") (pintype "input"))
    )
    (net (code "167") (name "~{AD06}") (class "Default")
      (node (ref "E23") (pin "1") (pinfunction "D3_1") (pintype "input"))
      (node (ref "E28") (pin "2") (pinfunction "D2_2") (pintype "input"))
      (node (ref "E33") (pin "4") (pinfunction "D0_4") (pintype "input"))
      (node (ref "E37") (pin "6") (pinfunction "S2_6") (pintype "output"))
      (node (ref "E38") (pin "15") (pinfunction "D4_15") (pintype "input"))
      (node (ref "E43") (pin "14") (pinfunction "D5_14") (pintype "input"))
      (node (ref "E6") (pin "3") (pinfunction "D1_3") (pintype "input"))
    )
    (net (code "168") (name "~{AD07}") (class "Default")
      (node (ref "E11") (pin "3") (pinfunction "D1_3") (pintype "input"))
      (node (ref "E28") (pin "1") (pinfunction "D3_1") (pintype "input"))
      (node (ref "E33") (pin "2") (pinfunction "D2_2") (pintype "input"))
      (node (ref "E37") (pin "9") (pinfunction "S1_9") (pintype "output"))
      (node (ref "E38") (pin "4") (pinfunction "D0_4") (pintype "input"))
      (node (ref "E43") (pin "15") (pinfunction "D4_15") (pintype "input"))
      (node (ref "E48") (pin "14") (pinfunction "D5_14") (pintype "input"))
    )
    (net (code "169") (name "~{AD08}") (class "Default")
      (node (ref "E16") (pin "3") (pinfunction "D1_3") (pintype "input"))
      (node (ref "E33") (pin "1") (pinfunction "D3_1") (pintype "input"))
      (node (ref "E38") (pin "2") (pinfunction "D2_2") (pintype "input"))
      (node (ref "E43") (pin "4") (pinfunction "D0_4") (pintype "input"))
      (node (ref "E48") (pin "15") (pinfunction "D4_15") (pintype "input"))
      (node (ref "E52") (pin "15") (pinfunction "S4_15") (pintype "output"))
      (node (ref "E53") (pin "14") (pinfunction "D5_14") (pintype "input"))
    )
    (net (code "170") (name "~{AD09}") (class "Default")
      (node (ref "E21") (pin "3") (pinfunction "D1_3") (pintype "input"))
      (node (ref "E38") (pin "1") (pinfunction "D3_1") (pintype "input"))
      (node (ref "E43") (pin "2") (pinfunction "D2_2") (pintype "input"))
      (node (ref "E48") (pin "4") (pinfunction "D0_4") (pintype "input"))
      (node (ref "E52") (pin "2") (pinfunction "S3_2") (pintype "output"))
      (node (ref "E53") (pin "15") (pinfunction "D4_15") (pintype "input"))
      (node (ref "E58") (pin "14") (pinfunction "D5_14") (pintype "input"))
    )
    (net (code "171") (name "~{AD10}") (class "Default")
      (node (ref "E23") (pin "3") (pinfunction "D1_3") (pintype "input"))
      (node (ref "E43") (pin "1") (pinfunction "D3_1") (pintype "input"))
      (node (ref "E48") (pin "2") (pinfunction "D2_2") (pintype "input"))
      (node (ref "E52") (pin "6") (pinfunction "S2_6") (pintype "output"))
      (node (ref "E53") (pin "4") (pinfunction "D0_4") (pintype "input"))
      (node (ref "E58") (pin "15") (pinfunction "D4_15") (pintype "input"))
      (node (ref "H") (pin "M1") (pinfunction "P_M1") (pintype "passive"))
    )
    (net (code "172") (name "~{AD11}") (class "Default")
      (node (ref "E17") (pin "4") (pinfunction "D_4") (pintype "input"))
      (node (ref "E28") (pin "3") (pinfunction "D1_3") (pintype "input"))
      (node (ref "E48") (pin "1") (pinfunction "D3_1") (pintype "input"))
      (node (ref "E52") (pin "9") (pinfunction "S1_9") (pintype "output"))
      (node (ref "E53") (pin "2") (pinfunction "D2_2") (pintype "input"))
      (node (ref "E58") (pin "4") (pinfunction "D0_4") (pintype "input"))
      (node (ref "E6") (pin "14") (pinfunction "D5_14") (pintype "input"))
      (node (ref "H") (pin "N1") (pinfunction "P_N1") (pintype "passive"))
    )
    (net (code "173") (name "~{ADLK}") (class "Default")
      (node (ref "E11") (pin "14") (pinfunction "D5_14") (pintype "input"))
      (node (ref "E53") (pin "1") (pinfunction "D3_1") (pintype "input"))
      (node (ref "E58") (pin "2") (pinfunction "D2_2") (pintype "input"))
      (node (ref "E6") (pin "15") (pinfunction "D4_15") (pintype "input"))
      (node (ref "H") (pin "L1") (pinfunction "P_L1") (pintype "passive"))
    )
    (net (code "174") (name "~{AL2MQ_ENA}") (class "Default")
      (node (ref "E") (pin "T1") (pinfunction "P_T1") (pintype "passive"))
      (node (ref "E12") (pin "7") (pinfunction "S1_7") (pintype "input"))
      (node (ref "E34") (pin "7") (pinfunction "S1_7") (pintype "input"))
      (node (ref "E59") (pin "7") (pinfunction "S1_7") (pintype "input"))
    )
    (net (code "175") (name "~{AND00}") (class "Default")
      (node (ref "E13") (pin "3") (pinfunction "O_3") (pintype "output"))
      (node (ref "E6") (pin "13") (pinfunction "D6_13") (pintype "input"))
    )
    (net (code "176") (name "~{AND01}") (class "Default")
      (node (ref "E11") (pin "13") (pinfunction "D6_13") (pintype "input"))
      (node (ref "E13") (pin "6") (pinfunction "O_6") (pintype "output"))
    )
    (net (code "177") (name "~{AND02}") (class "Default")
      (node (ref "E13") (pin "11") (pinfunction "O_11") (pintype "output"))
      (node (ref "E16") (pin "13") (pinfunction "D6_13") (pintype "input"))
    )
    (net (code "178") (name "~{AND03}") (class "Default")
      (node (ref "E13") (pin "8") (pinfunction "O_8") (pintype "output"))
      (node (ref "E21") (pin "13") (pinfunction "D6_13") (pintype "input"))
    )
    (net (code "179") (name "~{AND04}") (class "Default")
      (node (ref "E23") (pin "13") (pinfunction "D6_13") (pintype "input"))
      (node (ref "E35") (pin "3") (pinfunction "O_3") (pintype "output"))
    )
    (net (code "180") (name "~{AND05}") (class "Default")
      (node (ref "E28") (pin "13") (pinfunction "D6_13") (pintype "input"))
      (node (ref "E35") (pin "6") (pinfunction "O_6") (pintype "output"))
    )
    (net (code "181") (name "~{AND06}") (class "Default")
      (node (ref "E33") (pin "13") (pinfunction "D6_13") (pintype "input"))
      (node (ref "E35") (pin "11") (pinfunction "O_11") (pintype "output"))
    )
    (net (code "182") (name "~{AND07}") (class "Default")
      (node (ref "E35") (pin "8") (pinfunction "O_8") (pintype "output"))
      (node (ref "E38") (pin "13") (pinfunction "D6_13") (pintype "input"))
    )
    (net (code "183") (name "~{AND08}") (class "Default")
      (node (ref "E43") (pin "13") (pinfunction "D6_13") (pintype "input"))
      (node (ref "E61") (pin "3") (pinfunction "O_3") (pintype "output"))
    )
    (net (code "184") (name "~{AND09}") (class "Default")
      (node (ref "E48") (pin "13") (pinfunction "D6_13") (pintype "input"))
      (node (ref "E61") (pin "6") (pinfunction "O_6") (pintype "output"))
    )
    (net (code "185") (name "~{AND10}") (class "Default")
      (node (ref "E53") (pin "13") (pinfunction "D6_13") (pintype "input"))
      (node (ref "E61") (pin "11") (pinfunction "O_11") (pintype "output"))
    )
    (net (code "186") (name "~{AND11}") (class "Default")
      (node (ref "E58") (pin "13") (pinfunction "D6_13") (pintype "input"))
      (node (ref "E61") (pin "8") (pinfunction "O_8") (pintype "output"))
    )
    (net (code "187") (name "~{B00}") (class "Default")
      (node (ref "E10") (pin "12") (pinfunction "F3_12") (pintype "output"))
      (node (ref "E15") (pin "1") (pinfunction "A4_1") (pintype "input"))
    )
    (net (code "188") (name "~{B01}") (class "Default")
      (node (ref "E10") (pin "9") (pinfunction "F2_9") (pintype "output"))
      (node (ref "E15") (pin "3") (pinfunction "A3_3") (pintype "input"))
    )
    (net (code "189") (name "~{B02}") (class "Default")
      (node (ref "E10") (pin "3") (pinfunction "F0_3") (pintype "output"))
      (node (ref "E15") (pin "7") (pinfunction "B2_7") (pintype "input"))
    )
    (net (code "190") (name "~{B03}") (class "Default")
      (node (ref "E10") (pin "6") (pinfunction "F1_6") (pintype "output"))
      (node (ref "E15") (pin "11") (pinfunction "B1_11") (pintype "input"))
    )
    (net (code "191") (name "~{B04}") (class "Default")
      (node (ref "E31") (pin "3") (pinfunction "F0_3") (pintype "output"))
      (node (ref "E37") (pin "1") (pinfunction "A4_1") (pintype "input"))
    )
    (net (code "192") (name "~{B05}") (class "Default")
      (node (ref "E31") (pin "12") (pinfunction "F3_12") (pintype "output"))
      (node (ref "E37") (pin "3") (pinfunction "A3_3") (pintype "input"))
    )
    (net (code "193") (name "~{B06}") (class "Default")
      (node (ref "E31") (pin "9") (pinfunction "F2_9") (pintype "output"))
      (node (ref "E37") (pin "7") (pinfunction "B2_7") (pintype "input"))
    )
    (net (code "194") (name "~{B07}") (class "Default")
      (node (ref "E31") (pin "6") (pinfunction "F1_6") (pintype "output"))
      (node (ref "E37") (pin "11") (pinfunction "B1_11") (pintype "input"))
    )
    (net (code "195") (name "~{B08}") (class "Default")
      (node (ref "E52") (pin "16") (pinfunction "B4_16") (pintype "input"))
      (node (ref "E57") (pin "3") (pinfunction "F0_3") (pintype "output"))
    )
    (net (code "196") (name "~{B09}") (class "Default")
      (node (ref "E52") (pin "3") (pinfunction "A3_3") (pintype "input"))
      (node (ref "E57") (pin "12") (pinfunction "F3_12") (pintype "output"))
    )
    (net (code "197") (name "~{B10}") (class "Default")
      (node (ref "E52") (pin "7") (pinfunction "B2_7") (pintype "input"))
      (node (ref "E57") (pin "9") (pinfunction "F2_9") (pintype "output"))
    )
    (net (code "198") (name "~{B11}") (class "Default")
      (node (ref "E52") (pin "11") (pinfunction "B1_11") (pintype "input"))
      (node (ref "E57") (pin "6") (pinfunction "F1_6") (pintype "output"))
    )
    (net (code "199") (name "~{B_INIT}") (class "Default")
      (node (ref "E29") (pin "1") (pinfunction "R_1") (pintype "input"))
      (node (ref "E55") (pin "1") (pinfunction "R_1") (pintype "input"))
      (node (ref "E63") (pin "12") (pinfunction "O_12") (pintype "output"))
      (node (ref "E8") (pin "1") (pinfunction "R_1") (pintype "input"))
    )
    (net (code "200") (name "~{CARRY04}") (class "Default")
      (node (ref "E15") (pin "13") (pinfunction "C0_13") (pintype "input"))
      (node (ref "E37") (pin "14") (pinfunction "C4_14") (pintype "output"))
    )
    (net (code "201") (name "~{CARRY08}") (class "Default")
      (node (ref "E37") (pin "13") (pinfunction "C0_13") (pintype "input"))
      (node (ref "E52") (pin "14") (pinfunction "C4_14") (pintype "output"))
    )
    (net (code "202") (name "~{CARRY_IN}") (class "Default")
      (node (ref "E52") (pin "13") (pinfunction "C0_13") (pintype "input"))
      (node (ref "H") (pin "M2") (pinfunction "P_M2") (pintype "passive"))
    )
    (net (code "203") (name "~{CARRY_OUT}") (class "Default")
      (node (ref "E") (pin "C1") (pinfunction "P_C1") (pintype "passive"))
      (node (ref "E15") (pin "14") (pinfunction "C4_14") (pintype "output"))
    )
    (net (code "204") (name "~{CPMA_LOAD}") (class "Default")
      (node (ref "E25") (pin "6") (pinfunction "C_6") (pintype "input"))
      (node (ref "E4") (pin "6") (pinfunction "C_6") (pintype "input"))
      (node (ref "E46") (pin "6") (pinfunction "C_6") (pintype "input"))
      (node (ref "H") (pin "E1") (pinfunction "P_E1") (pintype "passive"))
    )
    (net (code "205") (name "~{LEFT}") (class "Default")
      (node (ref "E64") (pin "11") (pinfunction "I_11") (pintype "input"))
      (node (ref "H") (pin "J2") (pinfunction "P_J2") (pintype "passive"))
    )
    (net (code "206") (name "~{MA00}") (class "Default")
      (node (ref "E1") (pin "10") (pinfunction "O_10") (pintype "open_collector"))
      (node (ref "E5") (pin "14") (pinfunction "B3_14") (pintype "input"))
      (node (ref "E9") (pin "3") (pinfunction "1C3_3") (pintype "input"))
      (node (ref "U$2") (pin "AD1") (pinfunction "1_AD1") (pintype "bidirectional"))
    )
    (net (code "207") (name "~{MA01}") (class "Default")
      (node (ref "E1") (pin "13") (pinfunction "O_13") (pintype "open_collector"))
      (node (ref "E5") (pin "11") (pinfunction "B2_11") (pintype "input"))
      (node (ref "E9") (pin "13") (pinfunction "2C3_13") (pintype "input"))
      (node (ref "U$2") (pin "AE1") (pinfunction "1_AE1") (pintype "bidirectional"))
    )
    (net (code "208") (name "~{MA02}") (class "Default")
      (node (ref "E1") (pin "4") (pinfunction "O_4") (pintype "open_collector"))
      (node (ref "E19") (pin "3") (pinfunction "1C3_3") (pintype "input"))
      (node (ref "E5") (pin "2") (pinfunction "B0_2") (pintype "input"))
      (node (ref "U$2") (pin "AH1") (pinfunction "1_AH1") (pintype "bidirectional"))
    )
    (net (code "209") (name "~{MA03}") (class "Default")
      (node (ref "E1") (pin "1") (pinfunction "O_1") (pintype "open_collector"))
      (node (ref "E19") (pin "13") (pinfunction "2C3_13") (pintype "input"))
      (node (ref "E5") (pin "5") (pinfunction "B1_5") (pintype "input"))
      (node (ref "U$2") (pin "AJ1") (pinfunction "1_AJ1") (pintype "bidirectional"))
    )
    (net (code "210") (name "~{MA04}") (class "Default")
      (node (ref "E22") (pin "10") (pinfunction "O_10") (pintype "open_collector"))
      (node (ref "E26") (pin "14") (pinfunction "B3_14") (pintype "input"))
      (node (ref "E30") (pin "3") (pinfunction "1C3_3") (pintype "input"))
      (node (ref "U$2") (pin "BD1") (pinfunction "1_BD1") (pintype "bidirectional"))
    )
    (net (code "211") (name "~{MA05}") (class "Default")
      (node (ref "E22") (pin "13") (pinfunction "O_13") (pintype "open_collector"))
      (node (ref "E30") (pin "13") (pinfunction "2C3_13") (pintype "input"))
      (node (ref "U$2") (pin "BE1") (pinfunction "1_BE1") (pintype "bidirectional"))
    )
    (net (code "212") (name "~{MA06}") (class "Default")
      (node (ref "E22") (pin "4") (pinfunction "O_4") (pintype "open_collector"))
      (node (ref "E41") (pin "3") (pinfunction "1C3_3") (pintype "input"))
      (node (ref "U$2") (pin "BH1") (pinfunction "1_BH1") (pintype "bidirectional"))
    )
    (net (code "213") (name "~{MA07}") (class "Default")
      (node (ref "E22") (pin "1") (pinfunction "O_1") (pintype "open_collector"))
      (node (ref "E41") (pin "13") (pinfunction "2C3_13") (pintype "input"))
      (node (ref "U$2") (pin "BJ1") (pinfunction "1_BJ1") (pintype "bidirectional"))
    )
    (net (code "214") (name "~{MA08}") (class "Default")
      (node (ref "E44") (pin "10") (pinfunction "O_10") (pintype "open_collector"))
      (node (ref "E51") (pin "3") (pinfunction "1C3_3") (pintype "input"))
      (node (ref "U$2") (pin "DD1") (pinfunction "1_DD1") (pintype "bidirectional"))
    )
    (net (code "215") (name "~{MA09}") (class "Default")
      (node (ref "E44") (pin "13") (pinfunction "O_13") (pintype "open_collector"))
      (node (ref "E51") (pin "13") (pinfunction "2C3_13") (pintype "input"))
      (node (ref "U$2") (pin "DE1") (pinfunction "1_DE1") (pintype "bidirectional"))
    )
    (net (code "216") (name "~{MA10}") (class "Default")
      (node (ref "E44") (pin "4") (pinfunction "O_4") (pintype "open_collector"))
      (node (ref "E62") (pin "3") (pinfunction "1C3_3") (pintype "input"))
      (node (ref "U$2") (pin "DH1") (pinfunction "1_DH1") (pintype "bidirectional"))
    )
    (net (code "217") (name "~{MA11}") (class "Default")
      (node (ref "E44") (pin "1") (pinfunction "O_1") (pintype "open_collector"))
      (node (ref "E62") (pin "13") (pinfunction "2C3_13") (pintype "input"))
      (node (ref "U$2") (pin "DJ1") (pinfunction "1_DJ1") (pintype "bidirectional"))
    )
    (net (code "218") (name "~{MAC}") (class "Default")
      (node (ref "E64") (pin "5") (pinfunction "I_5") (pintype "input"))
      (node (ref "H") (pin "A1") (pinfunction "P_A1") (pintype "passive"))
    )
    (net (code "219") (name "~{MB_LOAD}") (class "Default")
      (node (ref "E24") (pin "6") (pinfunction "C_6") (pintype "input"))
      (node (ref "E3") (pin "6") (pinfunction "C_6") (pintype "input"))
      (node (ref "E50") (pin "6") (pinfunction "C_6") (pintype "input"))
      (node (ref "H") (pin "F1") (pinfunction "P_F1") (pintype "passive"))
    )
    (net (code "220") (name "~{MD00}") (class "Default")
      (node (ref "E2") (pin "10") (pinfunction "O_10") (pintype "open_collector"))
      (node (ref "E9") (pin "5") (pinfunction "1C1_5") (pintype "input"))
      (node (ref "U$2") (pin "AK1") (pinfunction "1_AK1") (pintype "bidirectional"))
    )
    (net (code "221") (name "~{MD01}") (class "Default")
      (node (ref "E2") (pin "13") (pinfunction "O_13") (pintype "open_collector"))
      (node (ref "E9") (pin "11") (pinfunction "2C1_11") (pintype "input"))
      (node (ref "U$2") (pin "AL1") (pinfunction "1_AL1") (pintype "bidirectional"))
    )
    (net (code "222") (name "~{MD02}") (class "Default")
      (node (ref "E19") (pin "5") (pinfunction "1C1_5") (pintype "input"))
      (node (ref "E2") (pin "4") (pinfunction "O_4") (pintype "open_collector"))
      (node (ref "U$2") (pin "AM1") (pinfunction "1_AM1") (pintype "bidirectional"))
    )
    (net (code "223") (name "~{MD03}") (class "Default")
      (node (ref "E19") (pin "11") (pinfunction "2C1_11") (pintype "input"))
      (node (ref "E2") (pin "1") (pinfunction "O_1") (pintype "open_collector"))
      (node (ref "U$2") (pin "AP1") (pinfunction "1_AP1") (pintype "bidirectional"))
    )
    (net (code "224") (name "~{MD04}") (class "Default")
      (node (ref "E27") (pin "10") (pinfunction "O_10") (pintype "open_collector"))
      (node (ref "E30") (pin "5") (pinfunction "1C1_5") (pintype "input"))
      (node (ref "U$2") (pin "BK1") (pinfunction "1_BK1") (pintype "bidirectional"))
    )
    (net (code "225") (name "~{MD05}") (class "Default")
      (node (ref "E27") (pin "13") (pinfunction "O_13") (pintype "open_collector"))
      (node (ref "E28") (pin "12") (pinfunction "D7_12") (pintype "input"))
      (node (ref "E30") (pin "11") (pinfunction "2C1_11") (pintype "input"))
      (node (ref "U$2") (pin "BL1") (pinfunction "1_BL1") (pintype "bidirectional"))
    )
    (net (code "226") (name "~{MD06}") (class "Default")
      (node (ref "E27") (pin "4") (pinfunction "O_4") (pintype "open_collector"))
      (node (ref "E33") (pin "12") (pinfunction "D7_12") (pintype "input"))
      (node (ref "E41") (pin "5") (pinfunction "1C1_5") (pintype "input"))
      (node (ref "U$2") (pin "BM1") (pinfunction "1_BM1") (pintype "bidirectional"))
    )
    (net (code "227") (name "~{MD07}") (class "Default")
      (node (ref "E27") (pin "1") (pinfunction "O_1") (pintype "open_collector"))
      (node (ref "E38") (pin "12") (pinfunction "D7_12") (pintype "input"))
      (node (ref "E41") (pin "11") (pinfunction "2C1_11") (pintype "input"))
      (node (ref "U$2") (pin "BP1") (pinfunction "1_BP1") (pintype "bidirectional"))
    )
    (net (code "228") (name "~{MD08}") (class "Default")
      (node (ref "E43") (pin "12") (pinfunction "D7_12") (pintype "input"))
      (node (ref "E49") (pin "10") (pinfunction "O_10") (pintype "open_collector"))
      (node (ref "E51") (pin "5") (pinfunction "1C1_5") (pintype "input"))
      (node (ref "U$2") (pin "DK1") (pinfunction "1_DK1") (pintype "bidirectional"))
    )
    (net (code "229") (name "~{MD09}") (class "Default")
      (node (ref "E48") (pin "12") (pinfunction "D7_12") (pintype "input"))
      (node (ref "E49") (pin "13") (pinfunction "O_13") (pintype "open_collector"))
      (node (ref "E51") (pin "11") (pinfunction "2C1_11") (pintype "input"))
      (node (ref "U$2") (pin "DL1") (pinfunction "1_DL1") (pintype "bidirectional"))
    )
    (net (code "230") (name "~{MD10}") (class "Default")
      (node (ref "E49") (pin "4") (pinfunction "O_4") (pintype "open_collector"))
      (node (ref "E53") (pin "12") (pinfunction "D7_12") (pintype "input"))
      (node (ref "E62") (pin "5") (pinfunction "1C1_5") (pintype "input"))
      (node (ref "U$2") (pin "DM1") (pinfunction "1_DM1") (pintype "bidirectional"))
    )
    (net (code "231") (name "~{MD11}") (class "Default")
      (node (ref "E49") (pin "1") (pinfunction "O_1") (pintype "open_collector"))
      (node (ref "E58") (pin "12") (pinfunction "D7_12") (pintype "input"))
      (node (ref "E62") (pin "11") (pinfunction "2C1_11") (pintype "input"))
      (node (ref "U$2") (pin "DP1") (pinfunction "1_DP1") (pintype "bidirectional"))
    )
    (net (code "232") (name "~{MD_DIR}") (class "Default")
      (node (ref "E63") (pin "1") (pinfunction "I_1") (pintype "input"))
      (node (ref "U$2") (pin "AK2") (pinfunction "1_AK2") (pintype "bidirectional"))
    )
    (net (code "233") (name "~{MQ00-03EQ0}") (class "Default")
      (node (ref "E") (pin "A1") (pinfunction "P_A1") (pintype "passive"))
      (node (ref "E18") (pin "8") (pinfunction "O_8") (pintype "output"))
    )
    (net (code "234") (name "~{MQ00}") (class "Default")
      (node (ref "E17") (pin "5") (pinfunction "Q0_5") (pintype "output"))
      (node (ref "E18") (pin "12") (pinfunction "I2_12") (pintype "input"))
      (node (ref "E7") (pin "11") (pinfunction "B2_11") (pintype "input"))
      (node (ref "E9") (pin "4") (pinfunction "1C2_4") (pintype "input"))
      (node (ref "H") (pin "V2") (pinfunction "P_V2") (pintype "passive"))
    )
    (net (code "235") (name "~{MQ01}") (class "Default")
      (node (ref "E12") (pin "5") (pinfunction "B1_5") (pintype "input"))
      (node (ref "E17") (pin "7") (pinfunction "Q1_7") (pintype "output"))
      (node (ref "E18") (pin "13") (pinfunction "I3_13") (pintype "input"))
      (node (ref "E7") (pin "14") (pinfunction "B3_14") (pintype "input"))
      (node (ref "E9") (pin "12") (pinfunction "2C2_12") (pintype "input"))
    )
    (net (code "236") (name "~{MQ2BUS}") (class "Default")
      (node (ref "E") (pin "D2") (pinfunction "P_D2") (pintype "passive"))
      (node (ref "E32") (pin "9") (pinfunction "S0_9") (pintype "input"))
      (node (ref "E60") (pin "9") (pinfunction "S0_9") (pintype "input"))
      (node (ref "E7") (pin "9") (pinfunction "S0_9") (pintype "input"))
    )
    (net (code "237") (name "~{MQ02}") (class "Default")
      (node (ref "E12") (pin "2") (pinfunction "B0_2") (pintype "input"))
      (node (ref "E17") (pin "9") (pinfunction "Q2_9") (pintype "output"))
      (node (ref "E18") (pin "10") (pinfunction "I1_10") (pintype "input"))
      (node (ref "E19") (pin "4") (pinfunction "1C2_4") (pintype "input"))
      (node (ref "E7") (pin "5") (pinfunction "B1_5") (pintype "input"))
    )
    (net (code "238") (name "~{MQ03}") (class "Default")
      (node (ref "E12") (pin "14") (pinfunction "B3_14") (pintype "input"))
      (node (ref "E17") (pin "11") (pinfunction "Q3_11") (pintype "output"))
      (node (ref "E18") (pin "9") (pinfunction "I0_9") (pintype "input"))
      (node (ref "E19") (pin "12") (pinfunction "2C2_12") (pintype "input"))
      (node (ref "E39") (pin "4") (pinfunction "D_4") (pintype "input"))
      (node (ref "E7") (pin "2") (pinfunction "B0_2") (pintype "input"))
    )
    (net (code "239") (name "~{MQ04-11EQ0}") (class "Default")
      (node (ref "E45") (pin "8") (pinfunction "O_8") (pintype "output"))
      (node (ref "H") (pin "K1") (pinfunction "P_K1") (pintype "passive"))
    )
    (net (code "240") (name "~{MQ04}") (class "Default")
      (node (ref "E12") (pin "11") (pinfunction "B2_11") (pintype "input"))
      (node (ref "E30") (pin "4") (pinfunction "1C2_4") (pintype "input"))
      (node (ref "E32") (pin "11") (pinfunction "B2_11") (pintype "input"))
      (node (ref "E39") (pin "5") (pinfunction "Q0_5") (pintype "output"))
      (node (ref "E45") (pin "12") (pinfunction "I7_12") (pintype "input"))
    )
    (net (code "241") (name "~{MQ05}") (class "Default")
      (node (ref "E30") (pin "12") (pinfunction "2C2_12") (pintype "input"))
      (node (ref "E32") (pin "14") (pinfunction "B3_14") (pintype "input"))
      (node (ref "E34") (pin "5") (pinfunction "B1_5") (pintype "input"))
      (node (ref "E39") (pin "7") (pinfunction "Q1_7") (pintype "output"))
      (node (ref "E45") (pin "11") (pinfunction "I6_11") (pintype "input"))
    )
    (net (code "242") (name "~{MQ06}") (class "Default")
      (node (ref "E32") (pin "5") (pinfunction "B1_5") (pintype "input"))
      (node (ref "E34") (pin "2") (pinfunction "B0_2") (pintype "input"))
      (node (ref "E39") (pin "9") (pinfunction "Q2_9") (pintype "output"))
      (node (ref "E41") (pin "4") (pinfunction "1C2_4") (pintype "input"))
      (node (ref "E45") (pin "5") (pinfunction "I4_5") (pintype "input"))
    )
    (net (code "243") (name "~{MQ07}") (class "Default")
      (node (ref "E32") (pin "2") (pinfunction "B0_2") (pintype "input"))
      (node (ref "E34") (pin "14") (pinfunction "B3_14") (pintype "input"))
      (node (ref "E39") (pin "11") (pinfunction "Q3_11") (pintype "output"))
      (node (ref "E41") (pin "12") (pinfunction "2C2_12") (pintype "input"))
      (node (ref "E45") (pin "6") (pinfunction "I5_6") (pintype "input"))
      (node (ref "E54") (pin "4") (pinfunction "D_4") (pintype "input"))
    )
    (net (code "244") (name "~{MQ08}") (class "Default")
      (node (ref "E34") (pin "11") (pinfunction "B2_11") (pintype "input"))
      (node (ref "E45") (pin "4") (pinfunction "I3_4") (pintype "input"))
      (node (ref "E51") (pin "4") (pinfunction "1C2_4") (pintype "input"))
      (node (ref "E54") (pin "5") (pinfunction "Q0_5") (pintype "output"))
      (node (ref "E60") (pin "5") (pinfunction "B1_5") (pintype "input"))
    )
    (net (code "245") (name "~{MQ09}") (class "Default")
      (node (ref "E45") (pin "3") (pinfunction "I2_3") (pintype "input"))
      (node (ref "E51") (pin "12") (pinfunction "2C2_12") (pintype "input"))
      (node (ref "E54") (pin "7") (pinfunction "Q1_7") (pintype "output"))
      (node (ref "E59") (pin "11") (pinfunction "B2_11") (pintype "input"))
      (node (ref "E60") (pin "2") (pinfunction "B0_2") (pintype "input"))
    )
    (net (code "246") (name "~{MQ10}") (class "Default")
      (node (ref "E45") (pin "2") (pinfunction "I1_2") (pintype "input"))
      (node (ref "E54") (pin "9") (pinfunction "Q2_9") (pintype "output"))
      (node (ref "E59") (pin "14") (pinfunction "B3_14") (pintype "input"))
      (node (ref "E60") (pin "11") (pinfunction "B2_11") (pintype "input"))
      (node (ref "E62") (pin "4") (pinfunction "1C2_4") (pintype "input"))
      (node (ref "H") (pin "J1") (pinfunction "P_J1") (pintype "passive"))
    )
    (net (code "247") (name "~{MQ11}") (class "Default")
      (node (ref "E45") (pin "1") (pinfunction "I0_1") (pintype "input"))
      (node (ref "E54") (pin "11") (pinfunction "Q3_11") (pintype "output"))
      (node (ref "E59") (pin "2") (pinfunction "B0_2") (pintype "input"))
      (node (ref "E60") (pin "14") (pinfunction "B3_14") (pintype "input"))
      (node (ref "E62") (pin "12") (pinfunction "2C2_12") (pintype "input"))
      (node (ref "H") (pin "H1") (pinfunction "P_H1") (pintype "passive"))
    )
    (net (code "248") (name "~{MQ_DATA}") (class "Default")
      (node (ref "E59") (pin "5") (pinfunction "B1_5") (pintype "input"))
      (node (ref "H") (pin "U2") (pinfunction "P_U2") (pintype "passive"))
    )
    (net (code "249") (name "~{MQ_LOAD}") (class "Default")
      (node (ref "E") (pin "E2") (pinfunction "P_E2") (pintype "passive"))
      (node (ref "E17") (pin "6") (pinfunction "C_6") (pintype "input"))
      (node (ref "E39") (pin "6") (pinfunction "C_6") (pintype "input"))
      (node (ref "E54") (pin "6") (pinfunction "C_6") (pintype "input"))
    )
    (net (code "250") (name "~{PC00}") (class "Default")
      (node (ref "E20") (pin "9") (pinfunction "Q2_9") (pintype "output"))
      (node (ref "E9") (pin "6") (pinfunction "1C0_6") (pintype "input"))
    )
    (net (code "251") (name "~{PC01}") (class "Default")
      (node (ref "E20") (pin "11") (pinfunction "Q3_11") (pintype "output"))
      (node (ref "E9") (pin "10") (pinfunction "2C0_10") (pintype "input"))
    )
    (net (code "252") (name "~{PC02}") (class "Default")
      (node (ref "E19") (pin "6") (pinfunction "1C0_6") (pintype "input"))
      (node (ref "E20") (pin "7") (pinfunction "Q1_7") (pintype "output"))
    )
    (net (code "253") (name "~{PC03}") (class "Default")
      (node (ref "E19") (pin "10") (pinfunction "2C0_10") (pintype "input"))
      (node (ref "E20") (pin "5") (pinfunction "Q0_5") (pintype "output"))
    )
    (net (code "254") (name "~{PC04}") (class "Default")
      (node (ref "E30") (pin "6") (pinfunction "1C0_6") (pintype "input"))
      (node (ref "E42") (pin "9") (pinfunction "Q2_9") (pintype "output"))
    )
    (net (code "255") (name "~{PC05}") (class "Default")
      (node (ref "E30") (pin "10") (pinfunction "2C0_10") (pintype "input"))
      (node (ref "E42") (pin "11") (pinfunction "Q3_11") (pintype "output"))
    )
    (net (code "256") (name "~{PC06}") (class "Default")
      (node (ref "E41") (pin "6") (pinfunction "1C0_6") (pintype "input"))
      (node (ref "E42") (pin "7") (pinfunction "Q1_7") (pintype "output"))
    )
    (net (code "257") (name "~{PC07}") (class "Default")
      (node (ref "E41") (pin "10") (pinfunction "2C0_10") (pintype "input"))
      (node (ref "E42") (pin "5") (pinfunction "Q0_5") (pintype "output"))
    )
    (net (code "258") (name "~{PC08}") (class "Default")
      (node (ref "E47") (pin "5") (pinfunction "Q0_5") (pintype "output"))
      (node (ref "E51") (pin "6") (pinfunction "1C0_6") (pintype "input"))
    )
    (net (code "259") (name "~{PC09}") (class "Default")
      (node (ref "E47") (pin "7") (pinfunction "Q1_7") (pintype "output"))
      (node (ref "E51") (pin "10") (pinfunction "2C0_10") (pintype "input"))
    )
    (net (code "260") (name "~{PC10}") (class "Default")
      (node (ref "E47") (pin "9") (pinfunction "Q2_9") (pintype "output"))
      (node (ref "E62") (pin "6") (pinfunction "1C0_6") (pintype "input"))
    )
    (net (code "261") (name "~{PC11}") (class "Default")
      (node (ref "E47") (pin "11") (pinfunction "Q3_11") (pintype "output"))
      (node (ref "E62") (pin "10") (pinfunction "2C0_10") (pintype "input"))
    )
    (net (code "262") (name "~{PC_LOAD}") (class "Default")
      (node (ref "C15") (pin "1") (pinfunction "1_1") (pintype "passive"))
      (node (ref "E20") (pin "6") (pinfunction "C_6") (pintype "input"))
      (node (ref "E42") (pin "6") (pinfunction "C_6") (pintype "input"))
      (node (ref "E47") (pin "6") (pinfunction "C_6") (pintype "input"))
      (node (ref "H") (pin "D1") (pinfunction "P_D1") (pintype "passive"))
    )
    (net (code "263") (name "~{PG00}") (class "Default")
      (node (ref "E5") (pin "13") (pinfunction "F3_13") (pintype "output"))
      (node (ref "E6") (pin "12") (pinfunction "D7_12") (pintype "input"))
    )
    (net (code "264") (name "~{PG01}") (class "Default")
      (node (ref "E11") (pin "12") (pinfunction "D7_12") (pintype "input"))
      (node (ref "E5") (pin "12") (pinfunction "F2_12") (pintype "output"))
    )
    (net (code "265") (name "~{PG02}") (class "Default")
      (node (ref "E16") (pin "12") (pinfunction "D7_12") (pintype "input"))
      (node (ref "E5") (pin "3") (pinfunction "F0_3") (pintype "output"))
    )
    (net (code "266") (name "~{PG03}") (class "Default")
      (node (ref "E21") (pin "12") (pinfunction "D7_12") (pintype "input"))
      (node (ref "E5") (pin "4") (pinfunction "F1_4") (pintype "output"))
    )
    (net (code "267") (name "~{PG04}") (class "Default")
      (node (ref "E23") (pin "12") (pinfunction "D7_12") (pintype "input"))
      (node (ref "E26") (pin "13") (pinfunction "F3_13") (pintype "output"))
    )
    (net (code "268") (name "~{REGBUS00}") (class "Default")
      (node (ref "E20") (pin "15") (pinfunction "I2_15") (pintype "input"))
      (node (ref "E6") (pin "5") (pinfunction "Y_5") (pintype "output"))
    )
    (net (code "269") (name "~{REGBUS01}") (class "Default")
      (node (ref "E11") (pin "5") (pinfunction "Y_5") (pintype "output"))
      (node (ref "E20") (pin "14") (pinfunction "I3_14") (pintype "input"))
    )
    (net (code "270") (name "~{REGBUS02}") (class "Default")
      (node (ref "E16") (pin "5") (pinfunction "Y_5") (pintype "output"))
      (node (ref "E20") (pin "2") (pinfunction "I1_2") (pintype "input"))
    )
    (net (code "271") (name "~{REGBUS03}") (class "Default")
      (node (ref "E20") (pin "3") (pinfunction "I0_3") (pintype "input"))
      (node (ref "E21") (pin "5") (pinfunction "Y_5") (pintype "output"))
    )
    (net (code "272") (name "~{REGBUS04}") (class "Default")
      (node (ref "E23") (pin "5") (pinfunction "Y_5") (pintype "output"))
      (node (ref "E42") (pin "15") (pinfunction "I2_15") (pintype "input"))
    )
    (net (code "273") (name "~{REGBUS05}") (class "Default")
      (node (ref "E28") (pin "5") (pinfunction "Y_5") (pintype "output"))
      (node (ref "E42") (pin "14") (pinfunction "I3_14") (pintype "input"))
    )
    (net (code "274") (name "~{REGBUS06}") (class "Default")
      (node (ref "E33") (pin "5") (pinfunction "Y_5") (pintype "output"))
      (node (ref "E42") (pin "2") (pinfunction "I1_2") (pintype "input"))
    )
    (net (code "275") (name "~{REGBUS07}") (class "Default")
      (node (ref "E38") (pin "5") (pinfunction "Y_5") (pintype "output"))
      (node (ref "E42") (pin "3") (pinfunction "I0_3") (pintype "input"))
    )
    (net (code "276") (name "~{REGBUS08}") (class "Default")
      (node (ref "E43") (pin "5") (pinfunction "Y_5") (pintype "output"))
      (node (ref "E47") (pin "3") (pinfunction "I0_3") (pintype "input"))
    )
    (net (code "277") (name "~{REGBUS09}") (class "Default")
      (node (ref "E47") (pin "2") (pinfunction "I1_2") (pintype "input"))
      (node (ref "E48") (pin "5") (pinfunction "Y_5") (pintype "output"))
    )
    (net (code "278") (name "~{REGBUS10}") (class "Default")
      (node (ref "E47") (pin "15") (pinfunction "I2_15") (pintype "input"))
      (node (ref "E53") (pin "5") (pinfunction "Y_5") (pintype "output"))
    )
    (net (code "279") (name "~{REGBUS11}") (class "Default")
      (node (ref "E47") (pin "14") (pinfunction "I3_14") (pintype "input"))
      (node (ref "E58") (pin "5") (pinfunction "Y_5") (pintype "output"))
    )
    (net (code "280") (name "~{RIGHT}") (class "Default")
      (node (ref "E63") (pin "9") (pinfunction "I_9") (pintype "input"))
      (node (ref "E64") (pin "9") (pinfunction "I_9") (pintype "input"))
      (node (ref "H") (pin "H2") (pinfunction "P_H2") (pintype "passive"))
    )
    (net (code "281") (name "~{SHL_ENA}") (class "Default")
      (node (ref "E") (pin "S2") (pinfunction "P_S2") (pintype "passive"))
      (node (ref "E12") (pin "9") (pinfunction "S0_9") (pintype "input"))
      (node (ref "E34") (pin "9") (pinfunction "S0_9") (pintype "input"))
      (node (ref "E59") (pin "9") (pinfunction "S0_9") (pintype "input"))
      (node (ref "R1") (pin "1") (pinfunction "1_1") (pintype "passive"))
    )
    (net (code "282") (name "~{TWICE}") (class "Default")
      (node (ref "E64") (pin "13") (pinfunction "I_13") (pintype "input"))
      (node (ref "H") (pin "K2") (pinfunction "P_K2") (pintype "passive"))
    )
  )
)
